# blimpy-2_0.net
KiCad netlist of a schematic drawn in EAGLE
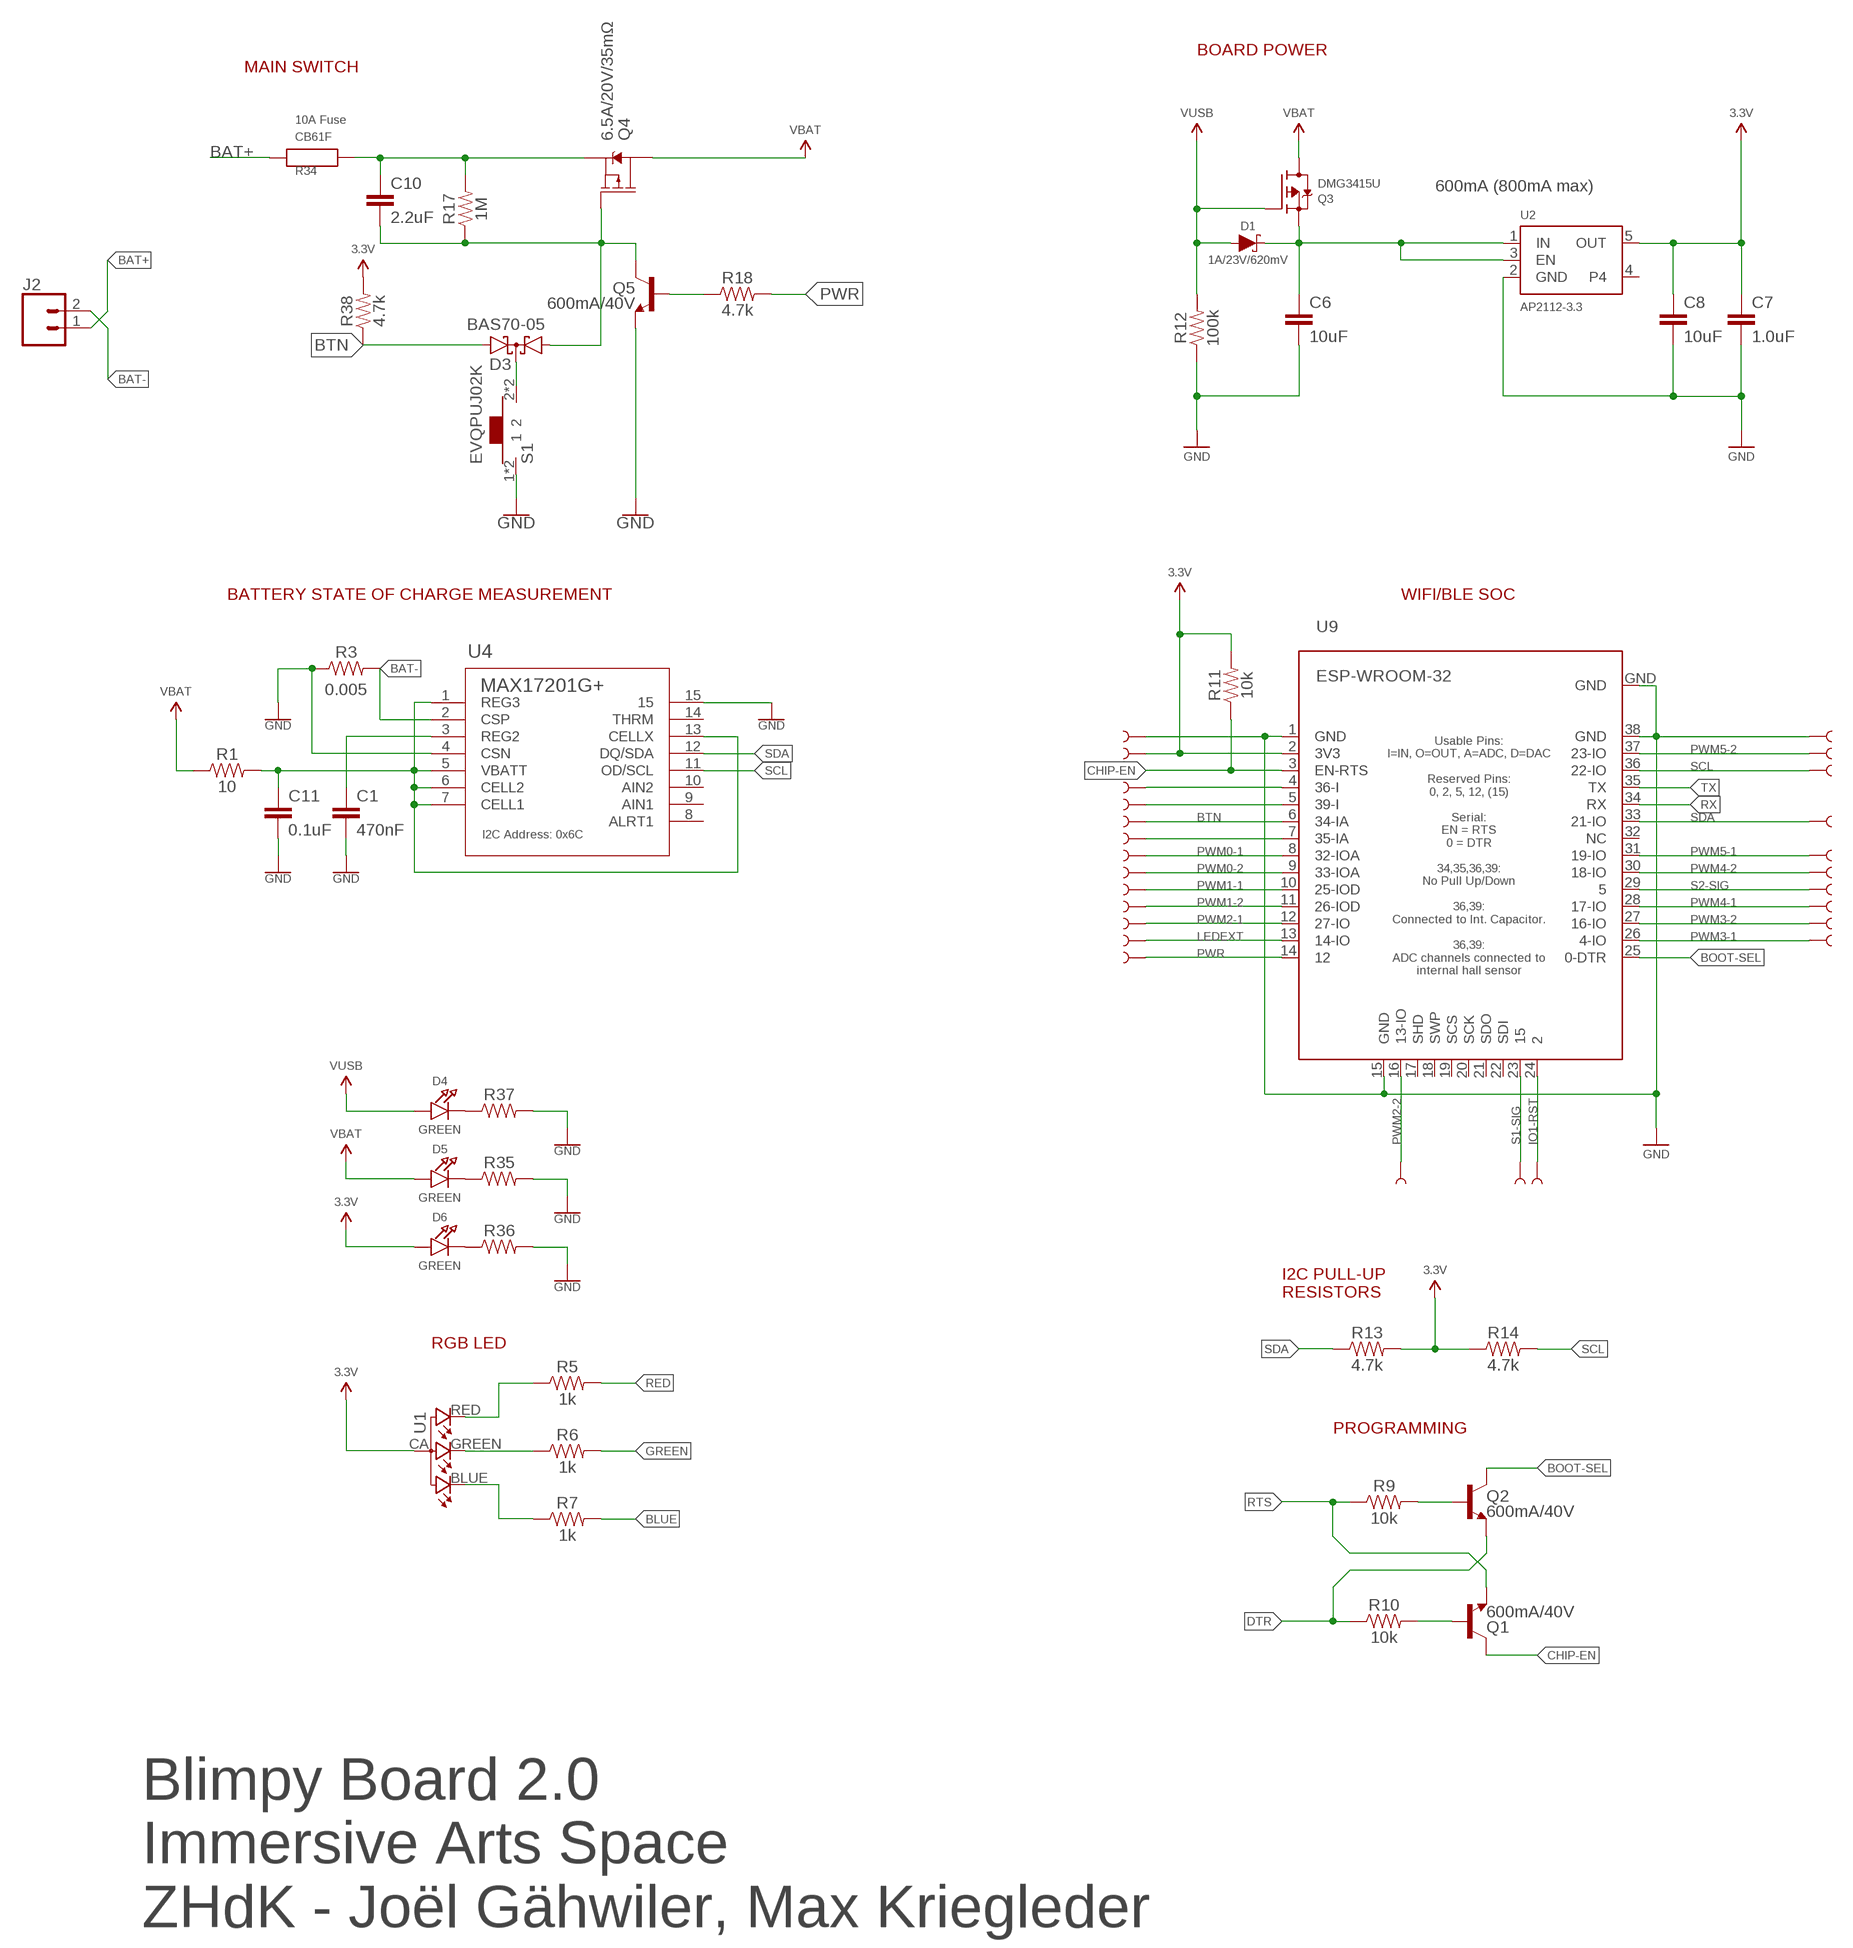
[diagram p0: schematic, sheet 1, part 1 of 2]
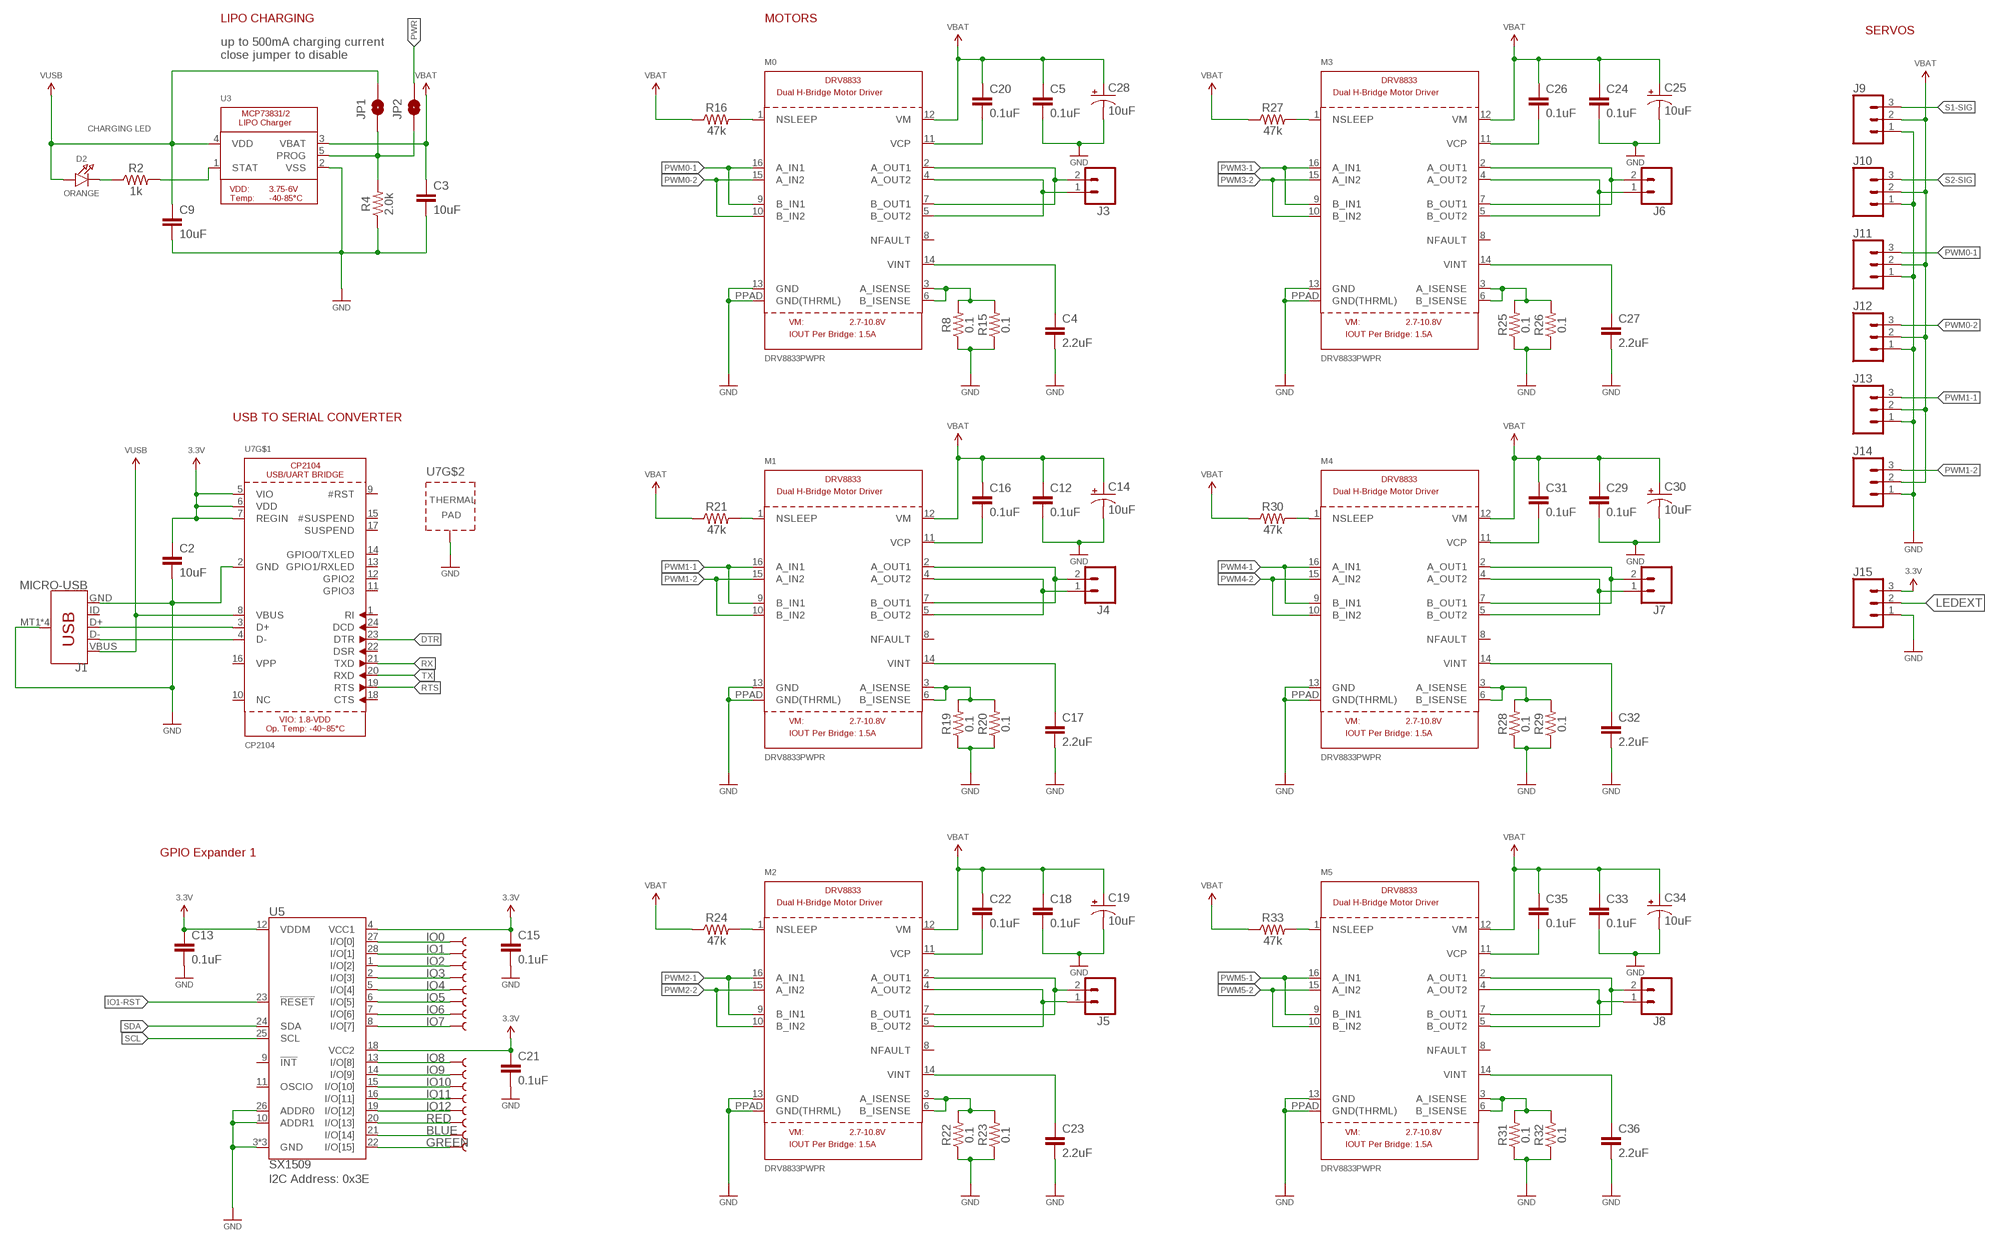
[diagram p1: schematic, sheet 1, part 2 of 2]

(export (version "E")
  (design (tool "Eeschema 10.0.6"))
  (components
    (comp (ref "C1")
      (value "470nF")
      (footprint "eagle-import:0603")
      (libsource (lib "eagle-import") (part "470NF-0608"))
    )
    (comp (ref "C2")
      (value "10uF")
      (footprint "eagle-import:0603")
      (libsource (lib "eagle-import") (part "10UF-0603-6.3V-20%"))
    )
    (comp (ref "C3")
      (value "10uF")
      (footprint "eagle-import:0603")
      (libsource (lib "eagle-import") (part "10UF-0603-6.3V-20%"))
    )
    (comp (ref "C4")
      (value "2.2uF")
      (footprint "eagle-import:0603")
      (libsource (lib "eagle-import") (part "2.2UF-0603-10V-20%"))
    )
    (comp (ref "C5")
      (value "0.1uF")
      (footprint "eagle-import:0603")
      (libsource (lib "eagle-import") (part "0.1UF-0603-25V-5%"))
    )
    (comp (ref "C6")
      (value "10uF")
      (footprint "eagle-import:0603")
      (libsource (lib "eagle-import") (part "10UF-0603-6.3V-20%"))
    )
    (comp (ref "C7")
      (value "1.0uF")
      (footprint "eagle-import:0603")
      (libsource (lib "eagle-import") (part "1.0UF-0603-16V-10%"))
    )
    (comp (ref "C8")
      (value "10uF")
      (footprint "eagle-import:0603")
      (libsource (lib "eagle-import") (part "10UF-0603-6.3V-20%"))
    )
    (comp (ref "C9")
      (value "10uF")
      (footprint "eagle-import:0603")
      (libsource (lib "eagle-import") (part "10UF-0603-6.3V-20%"))
    )
    (comp (ref "C10")
      (value "2.2uF")
      (footprint "eagle-import:0603")
      (libsource (lib "eagle-import") (part "2.2UF-0603-10V-20%"))
    )
    (comp (ref "C11")
      (value "0.1uF")
      (footprint "eagle-import:0603")
      (libsource (lib "eagle-import") (part "SparkFun-Capacitors_510_0.1UF-0603-25V-5%"))
    )
    (comp (ref "C12")
      (value "0.1uF")
      (footprint "eagle-import:0603")
      (libsource (lib "eagle-import") (part "0.1UF-0603-25V-5%"))
    )
    (comp (ref "C13")
      (value "0.1uF")
      (footprint "eagle-import:0603")
      (libsource (lib "eagle-import") (part "0.1UF-0603-25V-5%"))
    )
    (comp (ref "C14")
      (value "10uF")
      (footprint "eagle-import:EIA3216")
      (libsource (lib "eagle-import") (part "10UF-POLAR-EIA3216-16V-10%(TANT)"))
    )
    (comp (ref "C15")
      (value "0.1uF")
      (footprint "eagle-import:0603")
      (libsource (lib "eagle-import") (part "SparkFun-Capacitors_510_0.1UF-0603-25V-5%"))
    )
    (comp (ref "C16")
      (value "0.1uF")
      (footprint "eagle-import:0603")
      (libsource (lib "eagle-import") (part "0.1UF-0603-25V-5%"))
    )
    (comp (ref "C17")
      (value "2.2uF")
      (footprint "eagle-import:0603")
      (libsource (lib "eagle-import") (part "2.2UF-0603-10V-20%"))
    )
    (comp (ref "C18")
      (value "0.1uF")
      (footprint "eagle-import:0603")
      (libsource (lib "eagle-import") (part "0.1UF-0603-25V-5%"))
    )
    (comp (ref "C19")
      (value "10uF")
      (footprint "eagle-import:EIA3216")
      (libsource (lib "eagle-import") (part "10UF-POLAR-EIA3216-16V-10%(TANT)"))
    )
    (comp (ref "C20")
      (value "0.1uF")
      (footprint "eagle-import:0603")
      (libsource (lib "eagle-import") (part "0.1UF-0603-25V-5%"))
    )
    (comp (ref "C21")
      (value "0.1uF")
      (footprint "eagle-import:0603")
      (libsource (lib "eagle-import") (part "0.1UF-0603-25V-5%"))
    )
    (comp (ref "C22")
      (value "0.1uF")
      (footprint "eagle-import:0603")
      (libsource (lib "eagle-import") (part "0.1UF-0603-25V-5%"))
    )
    (comp (ref "C23")
      (value "2.2uF")
      (footprint "eagle-import:0603")
      (libsource (lib "eagle-import") (part "2.2UF-0603-10V-20%"))
    )
    (comp (ref "C24")
      (value "0.1uF")
      (footprint "eagle-import:0603")
      (libsource (lib "eagle-import") (part "0.1UF-0603-25V-5%"))
    )
    (comp (ref "C25")
      (value "10uF")
      (footprint "eagle-import:EIA3216")
      (libsource (lib "eagle-import") (part "10UF-POLAR-EIA3216-16V-10%(TANT)"))
    )
    (comp (ref "C26")
      (value "0.1uF")
      (footprint "eagle-import:0603")
      (libsource (lib "eagle-import") (part "0.1UF-0603-25V-5%"))
    )
    (comp (ref "C27")
      (value "2.2uF")
      (footprint "eagle-import:0603")
      (libsource (lib "eagle-import") (part "2.2UF-0603-10V-20%"))
    )
    (comp (ref "C28")
      (value "10uF")
      (footprint "eagle-import:EIA3216")
      (libsource (lib "eagle-import") (part "10UF-POLAR-EIA3216-16V-10%(TANT)"))
    )
    (comp (ref "C29")
      (value "0.1uF")
      (footprint "eagle-import:0603")
      (libsource (lib "eagle-import") (part "0.1UF-0603-25V-5%"))
    )
    (comp (ref "C30")
      (value "10uF")
      (footprint "eagle-import:EIA3216")
      (libsource (lib "eagle-import") (part "10UF-POLAR-EIA3216-16V-10%(TANT)"))
    )
    (comp (ref "C31")
      (value "0.1uF")
      (footprint "eagle-import:0603")
      (libsource (lib "eagle-import") (part "0.1UF-0603-25V-5%"))
    )
    (comp (ref "C32")
      (value "2.2uF")
      (footprint "eagle-import:0603")
      (libsource (lib "eagle-import") (part "2.2UF-0603-10V-20%"))
    )
    (comp (ref "C33")
      (value "0.1uF")
      (footprint "eagle-import:0603")
      (libsource (lib "eagle-import") (part "0.1UF-0603-25V-5%"))
    )
    (comp (ref "C34")
      (value "10uF")
      (footprint "eagle-import:EIA3216")
      (libsource (lib "eagle-import") (part "10UF-POLAR-EIA3216-16V-10%(TANT)"))
    )
    (comp (ref "C35")
      (value "0.1uF")
      (footprint "eagle-import:0603")
      (libsource (lib "eagle-import") (part "0.1UF-0603-25V-5%"))
    )
    (comp (ref "C36")
      (value "2.2uF")
      (footprint "eagle-import:0603")
      (libsource (lib "eagle-import") (part "2.2UF-0603-10V-20%"))
    )
    (comp (ref "D1")
      (value "1A/23V/620mV")
      (footprint "eagle-import:SOD-323")
      (libsource (lib "eagle-import") (part "DIODE-SCHOTTKY-BAT20J"))
    )
    (comp (ref "D2")
      (value "ORANGE")
      (footprint "eagle-import:CHIPLED_0805_NOOUTLINE")
      (libsource (lib "eagle-import") (part "LED0805_NOOUTLINE"))
    )
    (comp (ref "D3")
      (value "BAS70-05")
      (footprint "eagle-import:SOT23")
      (libsource (lib "eagle-import") (part "BAS70-05"))
    )
    (comp (ref "D4")
      (value "GREEN")
      (footprint "eagle-import:CHIPLED_0805_NOOUTLINE")
      (libsource (lib "eagle-import") (part "LED0805_NOOUTLINE"))
    )
    (comp (ref "D5")
      (value "GREEN")
      (footprint "eagle-import:CHIPLED_0805_NOOUTLINE")
      (libsource (lib "eagle-import") (part "LED0805_NOOUTLINE"))
    )
    (comp (ref "D6")
      (value "GREEN")
      (footprint "eagle-import:CHIPLED_0805_NOOUTLINE")
      (libsource (lib "eagle-import") (part "LED0805_NOOUTLINE"))
    )
    (comp (ref "J1")
      (value "MICRO-USB")
      (footprint "eagle-import:USB-MICROB")
      (libsource (lib "eagle-import") (part "USB_MICRO-B_SMT"))
    )
    (comp (ref "J2")
      (value "CONN_02PTH4")
      (footprint "eagle-import:1X02_XTRA_BIG")
      (libsource (lib "eagle-import") (part "CONN_02PTH4"))
    )
    (comp (ref "J3")
      (value "CONN_02-JST-2MM-SMT")
      (footprint "eagle-import:JST-2-SMD")
      (libsource (lib "eagle-import") (part "CONN_02-JST-2MM-SMT"))
    )
    (comp (ref "J4")
      (value "CONN_02-JST-2MM-SMT")
      (footprint "eagle-import:JST-2-SMD")
      (libsource (lib "eagle-import") (part "CONN_02-JST-2MM-SMT"))
    )
    (comp (ref "J5")
      (value "CONN_02-JST-2MM-SMT")
      (footprint "eagle-import:JST-2-SMD")
      (libsource (lib "eagle-import") (part "CONN_02-JST-2MM-SMT"))
    )
    (comp (ref "J6")
      (value "CONN_02-JST-2MM-SMT")
      (footprint "eagle-import:JST-2-SMD")
      (libsource (lib "eagle-import") (part "CONN_02-JST-2MM-SMT"))
    )
    (comp (ref "J7")
      (value "CONN_02-JST-2MM-SMT")
      (footprint "eagle-import:JST-2-SMD")
      (libsource (lib "eagle-import") (part "CONN_02-JST-2MM-SMT"))
    )
    (comp (ref "J8")
      (value "CONN_02-JST-2MM-SMT")
      (footprint "eagle-import:JST-2-SMD")
      (libsource (lib "eagle-import") (part "CONN_02-JST-2MM-SMT"))
    )
    (comp (ref "J9")
      (value "3-PIN SMD")
      (footprint "eagle-import:JST-3-SMD")
      (libsource (lib "eagle-import") (part "CONN_03JST-SMD"))
    )
    (comp (ref "J10")
      (value "3-PIN SMD")
      (footprint "eagle-import:JST-3-SMD")
      (libsource (lib "eagle-import") (part "CONN_03JST-SMD"))
    )
    (comp (ref "J11")
      (value "3-PIN SMD")
      (footprint "eagle-import:JST-3-SMD")
      (libsource (lib "eagle-import") (part "CONN_03JST-SMD"))
    )
    (comp (ref "J12")
      (value "3-PIN SMD")
      (footprint "eagle-import:JST-3-SMD")
      (libsource (lib "eagle-import") (part "CONN_03JST-SMD"))
    )
    (comp (ref "J13")
      (value "3-PIN SMD")
      (footprint "eagle-import:JST-3-SMD")
      (libsource (lib "eagle-import") (part "CONN_03JST-SMD"))
    )
    (comp (ref "J14")
      (value "3-PIN SMD")
      (footprint "eagle-import:JST-3-SMD")
      (libsource (lib "eagle-import") (part "CONN_03JST-SMD"))
    )
    (comp (ref "J15")
      (value "3-PIN SMD")
      (footprint "eagle-import:JST-3-SMD")
      (libsource (lib "eagle-import") (part "CONN_03JST-SMD"))
    )
    (comp (ref "JP1")
      (value "JUMPER-SMT_2_NO_SILK")
      (footprint "eagle-import:SMT-JUMPER_2_NO_SILK")
      (libsource (lib "eagle-import") (part "JUMPER-SMT_2_NO_SILK"))
    )
    (comp (ref "JP2")
      (value "JUMPER-SMT_2_NO_SILK")
      (footprint "eagle-import:SMT-JUMPER_2_NO_SILK")
      (libsource (lib "eagle-import") (part "JUMPER-SMT_2_NO_SILK"))
    )
    (comp (ref "M0")
      (value "DRV8833PWPR")
      (footprint "eagle-import:HTSSOP16")
      (libsource (lib "eagle-import") (part "DRV8833"))
    )
    (comp (ref "M1")
      (value "DRV8833PWPR")
      (footprint "eagle-import:HTSSOP16")
      (libsource (lib "eagle-import") (part "DRV8833"))
    )
    (comp (ref "M2")
      (value "DRV8833PWPR")
      (footprint "eagle-import:HTSSOP16")
      (libsource (lib "eagle-import") (part "DRV8833"))
    )
    (comp (ref "M3")
      (value "DRV8833PWPR")
      (footprint "eagle-import:HTSSOP16")
      (libsource (lib "eagle-import") (part "DRV8833"))
    )
    (comp (ref "M4")
      (value "DRV8833PWPR")
      (footprint "eagle-import:HTSSOP16")
      (libsource (lib "eagle-import") (part "DRV8833"))
    )
    (comp (ref "M5")
      (value "DRV8833PWPR")
      (footprint "eagle-import:HTSSOP16")
      (libsource (lib "eagle-import") (part "DRV8833"))
    )
    (comp (ref "Q1")
      (value "600mA/40V")
      (footprint "eagle-import:SOT23-3")
      (libsource (lib "eagle-import") (part "TRANS_NPN-MMBT2222AL"))
    )
    (comp (ref "Q2")
      (value "600mA/40V")
      (footprint "eagle-import:SOT23-3")
      (libsource (lib "eagle-import") (part "TRANS_NPN-MMBT2222AL"))
    )
    (comp (ref "Q3")
      (value "DMG3415U")
      (footprint "eagle-import:SOT23-R")
      (libsource (lib "eagle-import") (part "MOSFET-P"))
    )
    (comp (ref "Q4")
      (value "6.5A/20V/35mΩ")
      (footprint "eagle-import:SO08")
      (libsource (lib "eagle-import") (part "MOSFET_PCH-NDS8434"))
    )
    (comp (ref "Q5")
      (value "600mA/40V")
      (footprint "eagle-import:SOT23-3")
      (libsource (lib "eagle-import") (part "TRANS_NPN-MMBT2222AL"))
    )
    (comp (ref "R1")
      (value "10")
      (footprint "eagle-import:0603")
      (libsource (lib "eagle-import") (part "10OHM-0603-1/10W-1%"))
    )
    (comp (ref "R2")
      (value "1k")
      (footprint "eagle-import:0603")
      (libsource (lib "eagle-import") (part "1KOHM-0603-1/10W-1%"))
    )
    (comp (ref "R3")
      (value "0.005")
      (footprint "eagle-import:1206")
      (libsource (lib "eagle-import") (part "RESISTOR1206"))
    )
    (comp (ref "R4")
      (value "2.0k")
      (footprint "eagle-import:0603")
      (libsource (lib "eagle-import") (part "2.0KOHM-0603-1/10W-5%"))
    )
    (comp (ref "R5")
      (value "1k")
      (footprint "eagle-import:0603")
      (libsource (lib "eagle-import") (part "1KOHM-0603-1/10W-1%"))
    )
    (comp (ref "R6")
      (value "1k")
      (footprint "eagle-import:0603")
      (libsource (lib "eagle-import") (part "1KOHM-0603-1/10W-1%"))
    )
    (comp (ref "R7")
      (value "1k")
      (footprint "eagle-import:0603")
      (libsource (lib "eagle-import") (part "1KOHM-0603-1/10W-1%"))
    )
    (comp (ref "R8")
      (value "0.1")
      (footprint "eagle-import:1206")
      (libsource (lib "eagle-import") (part "RESISTOR1206"))
    )
    (comp (ref "R9")
      (value "10k")
      (footprint "eagle-import:0603")
      (libsource (lib "eagle-import") (part "10KOHM-0603-1/10W-1%"))
    )
    (comp (ref "R10")
      (value "10k")
      (footprint "eagle-import:0603")
      (libsource (lib "eagle-import") (part "10KOHM-0603-1/10W-1%"))
    )
    (comp (ref "R11")
      (value "10k")
      (footprint "eagle-import:0603")
      (libsource (lib "eagle-import") (part "10KOHM-0603-1/10W-1%"))
    )
    (comp (ref "R12")
      (value "100k")
      (footprint "eagle-import:0603")
      (libsource (lib "eagle-import") (part "100KOHM-0603-1/10W-1%"))
    )
    (comp (ref "R13")
      (value "4.7k")
      (footprint "eagle-import:0603")
      (libsource (lib "eagle-import") (part "4.7KOHM-0603-1/10W-1%"))
    )
    (comp (ref "R14")
      (value "4.7k")
      (footprint "eagle-import:0603")
      (libsource (lib "eagle-import") (part "4.7KOHM-0603-1/10W-1%"))
    )
    (comp (ref "R15")
      (value "0.1")
      (footprint "eagle-import:1206")
      (libsource (lib "eagle-import") (part "RESISTOR1206"))
    )
    (comp (ref "R16")
      (value "47k")
      (footprint "eagle-import:0603")
      (libsource (lib "eagle-import") (part "47KOHM-0603-1/10W-1%"))
    )
    (comp (ref "R17")
      (value "1M")
      (footprint "eagle-import:0603")
      (libsource (lib "eagle-import") (part "1MOHM-0603-1/4W-5%"))
    )
    (comp (ref "R18")
      (value "4.7k")
      (footprint "eagle-import:0603")
      (libsource (lib "eagle-import") (part "SparkFun-Resistors_532_4.7KOHM-0603-1/10W-1%"))
    )
    (comp (ref "R19")
      (value "0.1")
      (footprint "eagle-import:1206")
      (libsource (lib "eagle-import") (part "RESISTOR1206"))
    )
    (comp (ref "R20")
      (value "0.1")
      (footprint "eagle-import:1206")
      (libsource (lib "eagle-import") (part "RESISTOR1206"))
    )
    (comp (ref "R21")
      (value "47k")
      (footprint "eagle-import:0603")
      (libsource (lib "eagle-import") (part "47KOHM-0603-1/10W-1%"))
    )
    (comp (ref "R22")
      (value "0.1")
      (footprint "eagle-import:1206")
      (libsource (lib "eagle-import") (part "RESISTOR1206"))
    )
    (comp (ref "R23")
      (value "0.1")
      (footprint "eagle-import:1206")
      (libsource (lib "eagle-import") (part "RESISTOR1206"))
    )
    (comp (ref "R24")
      (value "47k")
      (footprint "eagle-import:0603")
      (libsource (lib "eagle-import") (part "47KOHM-0603-1/10W-1%"))
    )
    (comp (ref "R25")
      (value "0.1")
      (footprint "eagle-import:1206")
      (libsource (lib "eagle-import") (part "RESISTOR1206"))
    )
    (comp (ref "R26")
      (value "0.1")
      (footprint "eagle-import:1206")
      (libsource (lib "eagle-import") (part "RESISTOR1206"))
    )
    (comp (ref "R27")
      (value "47k")
      (footprint "eagle-import:0603")
      (libsource (lib "eagle-import") (part "47KOHM-0603-1/10W-1%"))
    )
    (comp (ref "R28")
      (value "0.1")
      (footprint "eagle-import:1206")
      (libsource (lib "eagle-import") (part "RESISTOR1206"))
    )
    (comp (ref "R29")
      (value "0.1")
      (footprint "eagle-import:1206")
      (libsource (lib "eagle-import") (part "RESISTOR1206"))
    )
    (comp (ref "R30")
      (value "47k")
      (footprint "eagle-import:0603")
      (libsource (lib "eagle-import") (part "47KOHM-0603-1/10W-1%"))
    )
    (comp (ref "R31")
      (value "0.1")
      (footprint "eagle-import:1206")
      (libsource (lib "eagle-import") (part "RESISTOR1206"))
    )
    (comp (ref "R32")
      (value "0.1")
      (footprint "eagle-import:1206")
      (libsource (lib "eagle-import") (part "RESISTOR1206"))
    )
    (comp (ref "R33")
      (value "47k")
      (footprint "eagle-import:0603")
      (libsource (lib "eagle-import") (part "47KOHM-0603-1/10W-1%"))
    )
    (comp (ref "R34")
      (value "CB61F")
      (footprint "eagle-import:CB61F")
      (libsource (lib "eagle-import") (part "CB61F"))
    )
    (comp (ref "R35")
      (value "RESISTOR0603")
      (footprint "eagle-import:0603")
      (libsource (lib "eagle-import") (part "RESISTOR0603"))
    )
    (comp (ref "R36")
      (value "RESISTOR0603")
      (footprint "eagle-import:0603")
      (libsource (lib "eagle-import") (part "RESISTOR0603"))
    )
    (comp (ref "R37")
      (value "RESISTOR0603")
      (footprint "eagle-import:0603")
      (libsource (lib "eagle-import") (part "RESISTOR0603"))
    )
    (comp (ref "R38")
      (value "4.7k")
      (footprint "eagle-import:0603")
      (libsource (lib "eagle-import") (part "1MOHM-0603-1/4W-5%"))
    )
    (comp (ref "S1")
      (value "EVQPUJ02K")
      (footprint "eagle-import:EVQPUJ02K")
      (libsource (lib "eagle-import") (part "EVQPUJ02K"))
    )
    (comp (ref "TP1")
      (value "TEST-POINT3")
      (footprint "eagle-import:PAD.03X.03")
      (libsource (lib "eagle-import") (part "TEST-POINT3"))
    )
    (comp (ref "TP2")
      (value "TEST-POINT3")
      (footprint "eagle-import:PAD.03X.03")
      (libsource (lib "eagle-import") (part "TEST-POINT3"))
    )
    (comp (ref "TP3")
      (value "TEST-POINT3")
      (footprint "eagle-import:PAD.03X.03")
      (libsource (lib "eagle-import") (part "TEST-POINT3"))
    )
    (comp (ref "TP4")
      (value "TEST-POINT3")
      (footprint "eagle-import:PAD.03X.03")
      (libsource (lib "eagle-import") (part "TEST-POINT3"))
    )
    (comp (ref "TP5")
      (value "TEST-POINT3")
      (footprint "eagle-import:PAD.03X.03")
      (libsource (lib "eagle-import") (part "TEST-POINT3"))
    )
    (comp (ref "TP6")
      (value "TEST-POINT3")
      (footprint "eagle-import:PAD.03X.03")
      (libsource (lib "eagle-import") (part "TEST-POINT3"))
    )
    (comp (ref "TP7")
      (value "TEST-POINT3")
      (footprint "eagle-import:PAD.03X.03")
      (libsource (lib "eagle-import") (part "TEST-POINT3"))
    )
    (comp (ref "TP8")
      (value "TEST-POINT3")
      (footprint "eagle-import:PAD.03X.03")
      (libsource (lib "eagle-import") (part "TEST-POINT3"))
    )
    (comp (ref "TP9")
      (value "TEST-POINT3")
      (footprint "eagle-import:PAD.03X.03")
      (libsource (lib "eagle-import") (part "TEST-POINT3"))
    )
    (comp (ref "TP10")
      (value "TEST-POINT3")
      (footprint "eagle-import:PAD.03X.03")
      (libsource (lib "eagle-import") (part "TEST-POINT3"))
    )
    (comp (ref "TP11")
      (value "TEST-POINT3")
      (footprint "eagle-import:PAD.03X.03")
      (libsource (lib "eagle-import") (part "TEST-POINT3"))
    )
    (comp (ref "TP12")
      (value "TEST-POINT3")
      (footprint "eagle-import:PAD.03X.03")
      (libsource (lib "eagle-import") (part "TEST-POINT3"))
    )
    (comp (ref "TP13")
      (value "TEST-POINT3")
      (footprint "eagle-import:PAD.03X.03")
      (libsource (lib "eagle-import") (part "TEST-POINT3"))
    )
    (comp (ref "TP14")
      (value "TEST-POINT3")
      (footprint "eagle-import:PAD.03X.03")
      (libsource (lib "eagle-import") (part "TEST-POINT3"))
    )
    (comp (ref "TP15")
      (value "TEST-POINT3")
      (footprint "eagle-import:PAD.03X.03")
      (libsource (lib "eagle-import") (part "TEST-POINT3"))
    )
    (comp (ref "TP16")
      (value "TEST-POINT3")
      (footprint "eagle-import:PAD.03X.03")
      (libsource (lib "eagle-import") (part "TEST-POINT3"))
    )
    (comp (ref "TP17")
      (value "TEST-POINT3")
      (footprint "eagle-import:PAD.03X.03")
      (libsource (lib "eagle-import") (part "TEST-POINT3"))
    )
    (comp (ref "TP18")
      (value "TEST-POINT3")
      (footprint "eagle-import:PAD.03X.03")
      (libsource (lib "eagle-import") (part "TEST-POINT3"))
    )
    (comp (ref "TP19")
      (value "TEST-POINT3")
      (footprint "eagle-import:PAD.03X.03")
      (libsource (lib "eagle-import") (part "TEST-POINT3"))
    )
    (comp (ref "TP20")
      (value "TEST-POINT3")
      (footprint "eagle-import:PAD.03X.03")
      (libsource (lib "eagle-import") (part "TEST-POINT3"))
    )
    (comp (ref "TP21")
      (value "TEST-POINT3")
      (footprint "eagle-import:PAD.03X.03")
      (libsource (lib "eagle-import") (part "TEST-POINT3"))
    )
    (comp (ref "TP22")
      (value "TEST-POINT3")
      (footprint "eagle-import:PAD.03X.03")
      (libsource (lib "eagle-import") (part "TEST-POINT3"))
    )
    (comp (ref "TP23")
      (value "TEST-POINT3")
      (footprint "eagle-import:PAD.03X.03")
      (libsource (lib "eagle-import") (part "TEST-POINT3"))
    )
    (comp (ref "TP24")
      (value "TEST-POINT3")
      (footprint "eagle-import:PAD.03X.03")
      (libsource (lib "eagle-import") (part "TEST-POINT3"))
    )
    (comp (ref "TP25")
      (value "TEST-POINT3")
      (footprint "eagle-import:PAD.03X.03")
      (libsource (lib "eagle-import") (part "TEST-POINT3"))
    )
    (comp (ref "TP26")
      (value "TEST-POINT3")
      (footprint "eagle-import:PAD.03X.03")
      (libsource (lib "eagle-import") (part "TEST-POINT3"))
    )
    (comp (ref "TP27")
      (value "TEST-POINT3")
      (footprint "eagle-import:PAD.03X.03")
      (libsource (lib "eagle-import") (part "TEST-POINT3"))
    )
    (comp (ref "TP28")
      (value "TEST-POINT3")
      (footprint "eagle-import:PAD.03X.03")
      (libsource (lib "eagle-import") (part "TEST-POINT3"))
    )
    (comp (ref "TP29")
      (value "TEST-POINT3")
      (footprint "eagle-import:PAD.03X.03")
      (libsource (lib "eagle-import") (part "TEST-POINT3"))
    )
    (comp (ref "TP30")
      (value "TEST-POINT3")
      (footprint "eagle-import:PAD.03X.03")
      (libsource (lib "eagle-import") (part "TEST-POINT3"))
    )
    (comp (ref "TP31")
      (value "TEST-POINT3")
      (footprint "eagle-import:PAD.03X.03")
      (libsource (lib "eagle-import") (part "TEST-POINT3"))
    )
    (comp (ref "TP32")
      (value "TEST-POINT3")
      (footprint "eagle-import:PAD.03X.03")
      (libsource (lib "eagle-import") (part "TEST-POINT3"))
    )
    (comp (ref "TP33")
      (value "TEST-POINT3")
      (footprint "eagle-import:PAD.03X.03")
      (libsource (lib "eagle-import") (part "TEST-POINT3"))
    )
    (comp (ref "TP34")
      (value "TEST-POINT3")
      (footprint "eagle-import:PAD.03X.03")
      (libsource (lib "eagle-import") (part "TEST-POINT3"))
    )
    (comp (ref "TP35")
      (value "TEST-POINT3")
      (footprint "eagle-import:PAD.03X.03")
      (libsource (lib "eagle-import") (part "TEST-POINT3"))
    )
    (comp (ref "TP36")
      (value "TEST-POINT3")
      (footprint "eagle-import:PAD.03X.03")
      (libsource (lib "eagle-import") (part "TEST-POINT3"))
    )
    (comp (ref "TP37")
      (value "TEST-POINT3")
      (footprint "eagle-import:PAD.03X.03")
      (libsource (lib "eagle-import") (part "TEST-POINT3"))
    )
    (comp (ref "TP38")
      (value "TEST-POINT3")
      (footprint "eagle-import:PAD.03X.03")
      (libsource (lib "eagle-import") (part "TEST-POINT3"))
    )
    (comp (ref "TP39")
      (value "TEST-POINT3")
      (footprint "eagle-import:PAD.03X.03")
      (libsource (lib "eagle-import") (part "TEST-POINT3"))
    )
    (comp (ref "TP40")
      (value "TEST-POINT3")
      (footprint "eagle-import:PAD.03X.03")
      (libsource (lib "eagle-import") (part "TEST-POINT3"))
    )
    (comp (ref "TP41")
      (value "TEST-POINT3")
      (footprint "eagle-import:PAD.03X.03")
      (libsource (lib "eagle-import") (part "TEST-POINT3"))
    )
    (comp (ref "TP42")
      (value "TEST-POINT3")
      (footprint "eagle-import:PAD.03X.03")
      (libsource (lib "eagle-import") (part "TEST-POINT3"))
    )
    (comp (ref "U1")
      (value "PARTICLE_RGB-LED-CLMVB-FKARGB")
      (footprint "eagle-import:PARTICLE_PLCC4-2MM-RGB")
      (libsource (lib "eagle-import") (part "PARTICLE_RGB-LED-CLMVB-FKARGB"))
    )
    (comp (ref "U2")
      (value "AP2112-3.3")
      (footprint "eagle-import:SOT23-5")
      (libsource (lib "eagle-import") (part "VREG_SOT23-5"))
    )
    (comp (ref "U3")
      (value "MICROBUILDER_MCP73831/2")
      (footprint "eagle-import:MICROBUILDER_SOT23-5")
      (libsource (lib "eagle-import") (part "MICROBUILDER_MCP73831/2"))
    )
    (comp (ref "U4")
      (value "MAX17201G+")
      (footprint "eagle-import:21-0137I_T1433-1_MXM")
      (fields (field (name "COPYRIGHT") "Copyright (C) 2018 Accelerated Designs. All rights reserved"))
      (libsource (lib "eagle-import") (part "MAX17201G+"))
    )
    (comp (ref "U5")
      (value "SX1509")
      (footprint "eagle-import:QFN-28")
      (libsource (lib "eagle-import") (part "SX1509"))
    )
    (comp (ref "U7")
      (value "CP2104")
      (footprint "eagle-import:QFN24_4MM_SMSC")
      (libsource (lib "eagle-import") (part "CP2104"))
    )
    (comp (ref "U9")
      (value "ESP-WROOM-32")
      (footprint "eagle-import:ESP-WROOM-32")
      (libsource (lib "eagle-import") (part "ESP-WROOM-32"))
    )
  )
  (nets
    (net (code "1") (name "/IO0") (class "Default")
      (node (ref "TP27") (pin "P$1") (pinfunction "1_P$1") (pintype "bidirectional"))
      (node (ref "U5") (pin "27") (pinfunction "I/O[0]_27") (pintype "bidirectional"))
    )
    (net (code "2") (name "/IO1") (class "Default")
      (node (ref "TP28") (pin "P$1") (pinfunction "1_P$1") (pintype "bidirectional"))
      (node (ref "U5") (pin "28") (pinfunction "I/O[1]_28") (pintype "bidirectional"))
    )
    (net (code "3") (name "/IO2") (class "Default")
      (node (ref "TP29") (pin "P$1") (pinfunction "1_P$1") (pintype "bidirectional"))
      (node (ref "U5") (pin "1") (pinfunction "I/O[2]_1") (pintype "bidirectional"))
    )
    (net (code "4") (name "/IO3") (class "Default")
      (node (ref "TP30") (pin "P$1") (pinfunction "1_P$1") (pintype "bidirectional"))
      (node (ref "U5") (pin "2") (pinfunction "I/O[3]_2") (pintype "bidirectional"))
    )
    (net (code "5") (name "/IO4") (class "Default")
      (node (ref "TP31") (pin "P$1") (pinfunction "1_P$1") (pintype "bidirectional"))
      (node (ref "U5") (pin "5") (pinfunction "I/O[4]_5") (pintype "bidirectional"))
    )
    (net (code "6") (name "/IO5") (class "Default")
      (node (ref "TP32") (pin "P$1") (pinfunction "1_P$1") (pintype "bidirectional"))
      (node (ref "U5") (pin "6") (pinfunction "I/O[5]_6") (pintype "bidirectional"))
    )
    (net (code "7") (name "/IO6") (class "Default")
      (node (ref "TP33") (pin "P$1") (pinfunction "1_P$1") (pintype "bidirectional"))
      (node (ref "U5") (pin "7") (pinfunction "I/O[6]_7") (pintype "bidirectional"))
    )
    (net (code "8") (name "/IO7") (class "Default")
      (node (ref "TP34") (pin "P$1") (pinfunction "1_P$1") (pintype "bidirectional"))
      (node (ref "U5") (pin "8") (pinfunction "I/O[7]_8") (pintype "bidirectional"))
    )
    (net (code "9") (name "/IO8") (class "Default")
      (node (ref "TP35") (pin "P$1") (pinfunction "1_P$1") (pintype "bidirectional"))
      (node (ref "U5") (pin "13") (pinfunction "I/O[8]_13") (pintype "bidirectional"))
    )
    (net (code "10") (name "/IO9") (class "Default")
      (node (ref "TP36") (pin "P$1") (pinfunction "1_P$1") (pintype "bidirectional"))
      (node (ref "U5") (pin "14") (pinfunction "I/O[9]_14") (pintype "bidirectional"))
    )
    (net (code "11") (name "/IO10") (class "Default")
      (node (ref "TP37") (pin "P$1") (pinfunction "1_P$1") (pintype "bidirectional"))
      (node (ref "U5") (pin "15") (pinfunction "I/O[10]_15") (pintype "bidirectional"))
    )
    (net (code "12") (name "/IO11") (class "Default")
      (node (ref "TP38") (pin "P$1") (pinfunction "1_P$1") (pintype "bidirectional"))
      (node (ref "U5") (pin "16") (pinfunction "I/O[11]_16") (pintype "bidirectional"))
    )
    (net (code "13") (name "/IO12") (class "Default")
      (node (ref "TP39") (pin "P$1") (pinfunction "1_P$1") (pintype "bidirectional"))
      (node (ref "U5") (pin "19") (pinfunction "I/O[12]_19") (pintype "bidirectional"))
    )
    (net (code "14") (name "3.3V") (class "Default")
      (node (ref "C13") (pin "1") (pinfunction "1_1") (pintype "passive"))
      (node (ref "C15") (pin "1") (pinfunction "1_1") (pintype "passive"))
      (node (ref "C2") (pin "1") (pinfunction "1_1") (pintype "passive"))
      (node (ref "C21") (pin "1") (pinfunction "1_1") (pintype "passive"))
      (node (ref "C7") (pin "1") (pinfunction "1_1") (pintype "passive"))
      (node (ref "C8") (pin "1") (pinfunction "1_1") (pintype "passive"))
      (node (ref "D6") (pin "A") (pinfunction "A_A") (pintype "passive"))
      (node (ref "J15") (pin "3") (pinfunction "3_3") (pintype "passive"))
      (node (ref "R11") (pin "2") (pinfunction "2_2") (pintype "passive"))
      (node (ref "R13") (pin "2") (pinfunction "2_2") (pintype "passive"))
      (node (ref "R14") (pin "1") (pinfunction "1_1") (pintype "passive"))
      (node (ref "R38") (pin "2") (pinfunction "2_2") (pintype "passive"))
      (node (ref "TP11") (pin "P$1") (pinfunction "1_P$1") (pintype "bidirectional"))
      (node (ref "U1") (pin "CA") (pinfunction "1_CA") (pintype "passive"))
      (node (ref "U2") (pin "5") (pinfunction "OUT_5") (pintype "power_in"))
      (node (ref "U5") (pin "12") (pinfunction "VDDM_12") (pintype "bidirectional"))
      (node (ref "U5") (pin "18") (pinfunction "VCC2_18") (pintype "bidirectional"))
      (node (ref "U5") (pin "4") (pinfunction "VCC1_4") (pintype "bidirectional"))
      (node (ref "U7") (pin "5") (pinfunction "VIO_5") (pintype "power_in"))
      (node (ref "U7") (pin "6") (pinfunction "VDD_6") (pintype "power_in"))
      (node (ref "U7") (pin "7") (pinfunction "REGIN_7") (pintype "power_in"))
      (node (ref "U9") (pin "2") (pinfunction "3V3_2") (pintype "bidirectional"))
    )
    (net (code "15") (name "BAT+") (class "Default")
      (node (ref "J2") (pin "1") (pinfunction "1_1") (pintype "passive"))
      (node (ref "R34") (pin "1") (pinfunction "1_1") (pintype "passive"))
    )
    (net (code "16") (name "BAT-") (class "Default")
      (node (ref "J2") (pin "2") (pinfunction "2_2") (pintype "passive"))
      (node (ref "R3") (pin "2") (pinfunction "2_2") (pintype "passive"))
      (node (ref "U4") (pin "2") (pinfunction "CSP_2") (pintype "passive"))
    )
    (net (code "17") (name "BLUE") (class "Default")
      (node (ref "R7") (pin "2") (pinfunction "2_2") (pintype "passive"))
      (node (ref "TP41") (pin "P$1") (pinfunction "1_P$1") (pintype "bidirectional"))
      (node (ref "U5") (pin "21") (pinfunction "I/O[14]_21") (pintype "bidirectional"))
    )
    (net (code "18") (name "BOOT-SEL") (class "Default")
      (node (ref "Q2") (pin "3") (pinfunction "C_3") (pintype "passive"))
      (node (ref "U9") (pin "25") (pinfunction "0-DTR_25") (pintype "bidirectional"))
    )
    (net (code "19") (name "BTN") (class "Default")
      (node (ref "D3") (pin "2") (pinfunction "A2_2") (pintype "passive"))
      (node (ref "R38") (pin "1") (pinfunction "1_1") (pintype "passive"))
      (node (ref "TP8") (pin "P$1") (pinfunction "1_P$1") (pintype "bidirectional"))
      (node (ref "U9") (pin "6") (pinfunction "34-IA_6") (pintype "bidirectional"))
    )
    (net (code "20") (name "CHIP-EN") (class "Default")
      (node (ref "Q1") (pin "3") (pinfunction "C_3") (pintype "passive"))
      (node (ref "R11") (pin "1") (pinfunction "1_1") (pintype "passive"))
      (node (ref "U9") (pin "3") (pinfunction "EN-RTS_3") (pintype "bidirectional"))
    )
    (net (code "21") (name "DTR") (class "Default")
      (node (ref "Q2") (pin "2") (pinfunction "E_2") (pintype "passive"))
      (node (ref "R10") (pin "1") (pinfunction "1_1") (pintype "passive"))
      (node (ref "U7") (pin "23") (pinfunction "DTR_23") (pintype "output"))
    )
    (net (code "22") (name "GND") (class "Default")
      (node (ref "C1") (pin "2") (pinfunction "2_2") (pintype "passive"))
      (node (ref "C11") (pin "2") (pinfunction "2_2") (pintype "passive"))
      (node (ref "C12") (pin "2") (pinfunction "2_2") (pintype "passive"))
      (node (ref "C13") (pin "2") (pinfunction "2_2") (pintype "passive"))
      (node (ref "C14") (pin "-") (pinfunction "-_-") (pintype "passive"))
      (node (ref "C15") (pin "2") (pinfunction "2_2") (pintype "passive"))
      (node (ref "C17") (pin "2") (pinfunction "2_2") (pintype "passive"))
      (node (ref "C18") (pin "2") (pinfunction "2_2") (pintype "passive"))
      (node (ref "C19") (pin "-") (pinfunction "-_-") (pintype "passive"))
      (node (ref "C2") (pin "2") (pinfunction "2_2") (pintype "passive"))
      (node (ref "C21") (pin "2") (pinfunction "2_2") (pintype "passive"))
      (node (ref "C23") (pin "2") (pinfunction "2_2") (pintype "passive"))
      (node (ref "C24") (pin "2") (pinfunction "2_2") (pintype "passive"))
      (node (ref "C25") (pin "-") (pinfunction "-_-") (pintype "passive"))
      (node (ref "C27") (pin "2") (pinfunction "2_2") (pintype "passive"))
      (node (ref "C28") (pin "-") (pinfunction "-_-") (pintype "passive"))
      (node (ref "C29") (pin "2") (pinfunction "2_2") (pintype "passive"))
      (node (ref "C3") (pin "2") (pinfunction "2_2") (pintype "passive"))
      (node (ref "C30") (pin "-") (pinfunction "-_-") (pintype "passive"))
      (node (ref "C32") (pin "2") (pinfunction "2_2") (pintype "passive"))
      (node (ref "C33") (pin "2") (pinfunction "2_2") (pintype "passive"))
      (node (ref "C34") (pin "-") (pinfunction "-_-") (pintype "passive"))
      (node (ref "C36") (pin "2") (pinfunction "2_2") (pintype "passive"))
      (node (ref "C4") (pin "2") (pinfunction "2_2") (pintype "passive"))
      (node (ref "C5") (pin "2") (pinfunction "2_2") (pintype "passive"))
      (node (ref "C6") (pin "2") (pinfunction "2_2") (pintype "passive"))
      (node (ref "C7") (pin "2") (pinfunction "2_2") (pintype "passive"))
      (node (ref "C8") (pin "2") (pinfunction "2_2") (pintype "passive"))
      (node (ref "C9") (pin "2") (pinfunction "2_2") (pintype "passive"))
      (node (ref "J1") (pin "GND") (pinfunction "GND_GND") (pintype "power_in"))
      (node (ref "J1") (pin "MT1") (pinfunction "SHIELD_MT1") (pintype "bidirectional"))
      (node (ref "J1") (pin "MT2") (pinfunction "SHIELD_MT2") (pintype "bidirectional"))
      (node (ref "J1") (pin "P$1") (pinfunction "SHIELD_P$1") (pintype "bidirectional"))
      (node (ref "J1") (pin "P$2") (pinfunction "SHIELD_P$2") (pintype "bidirectional"))
      (node (ref "J10") (pin "1") (pinfunction "1_1") (pintype "passive"))
      (node (ref "J11") (pin "1") (pinfunction "1_1") (pintype "passive"))
      (node (ref "J12") (pin "1") (pinfunction "1_1") (pintype "passive"))
      (node (ref "J13") (pin "1") (pinfunction "1_1") (pintype "passive"))
      (node (ref "J14") (pin "1") (pinfunction "1_1") (pintype "passive"))
      (node (ref "J15") (pin "1") (pinfunction "1_1") (pintype "passive"))
      (node (ref "J9") (pin "1") (pinfunction "1_1") (pintype "passive"))
      (node (ref "M0") (pin "13") (pinfunction "GND_13") (pintype "power_in"))
      (node (ref "M0") (pin "PPAD") (pinfunction "GND(THRML)_PPAD") (pintype "power_in"))
      (node (ref "M1") (pin "13") (pinfunction "GND_13") (pintype "power_in"))
      (node (ref "M1") (pin "PPAD") (pinfunction "GND(THRML)_PPAD") (pintype "power_in"))
      (node (ref "M2") (pin "13") (pinfunction "GND_13") (pintype "power_in"))
      (node (ref "M2") (pin "PPAD") (pinfunction "GND(THRML)_PPAD") (pintype "power_in"))
      (node (ref "M3") (pin "13") (pinfunction "GND_13") (pintype "power_in"))
      (node (ref "M3") (pin "PPAD") (pinfunction "GND(THRML)_PPAD") (pintype "power_in"))
      (node (ref "M4") (pin "13") (pinfunction "GND_13") (pintype "power_in"))
      (node (ref "M4") (pin "PPAD") (pinfunction "GND(THRML)_PPAD") (pintype "power_in"))
      (node (ref "M5") (pin "13") (pinfunction "GND_13") (pintype "power_in"))
      (node (ref "M5") (pin "PPAD") (pinfunction "GND(THRML)_PPAD") (pintype "power_in"))
      (node (ref "Q5") (pin "2") (pinfunction "E_2") (pintype "passive"))
      (node (ref "R12") (pin "1") (pinfunction "1_1") (pintype "passive"))
      (node (ref "R15") (pin "1") (pinfunction "1_1") (pintype "passive"))
      (node (ref "R19") (pin "1") (pinfunction "1_1") (pintype "passive"))
      (node (ref "R20") (pin "1") (pinfunction "1_1") (pintype "passive"))
      (node (ref "R22") (pin "1") (pinfunction "1_1") (pintype "passive"))
      (node (ref "R23") (pin "1") (pinfunction "1_1") (pintype "passive"))
      (node (ref "R25") (pin "1") (pinfunction "1_1") (pintype "passive"))
      (node (ref "R26") (pin "1") (pinfunction "1_1") (pintype "passive"))
      (node (ref "R28") (pin "1") (pinfunction "1_1") (pintype "passive"))
      (node (ref "R29") (pin "1") (pinfunction "1_1") (pintype "passive"))
      (node (ref "R3") (pin "1") (pinfunction "1_1") (pintype "passive"))
      (node (ref "R31") (pin "1") (pinfunction "1_1") (pintype "passive"))
      (node (ref "R32") (pin "1") (pinfunction "1_1") (pintype "passive"))
      (node (ref "R35") (pin "2") (pinfunction "2_2") (pintype "passive"))
      (node (ref "R36") (pin "2") (pinfunction "2_2") (pintype "passive"))
      (node (ref "R37") (pin "2") (pinfunction "2_2") (pintype "passive"))
      (node (ref "R4") (pin "1") (pinfunction "1_1") (pintype "passive"))
      (node (ref "R8") (pin "1") (pinfunction "1_1") (pintype "passive"))
      (node (ref "S1") (pin "1") (pinfunction "1_1") (pintype "bidirectional"))
      (node (ref "S1") (pin "3") (pinfunction "1_3") (pintype "bidirectional"))
      (node (ref "TP12") (pin "P$1") (pinfunction "1_P$1") (pintype "bidirectional"))
      (node (ref "TP13") (pin "P$1") (pinfunction "1_P$1") (pintype "bidirectional"))
      (node (ref "U2") (pin "2") (pinfunction "GND_2") (pintype "power_in"))
      (node (ref "U3") (pin "2") (pinfunction "VSS_2") (pintype "power_in"))
      (node (ref "U4") (pin "15") (pinfunction "15_15") (pintype "passive"))
      (node (ref "U4") (pin "4") (pinfunction "CSN_4") (pintype "passive"))
      (node (ref "U5") (pin "10") (pinfunction "ADDR1_10") (pintype "bidirectional"))
      (node (ref "U5") (pin "17") (pinfunction "GND_17") (pintype "bidirectional"))
      (node (ref "U5") (pin "26") (pinfunction "ADDR0_26") (pintype "bidirectional"))
      (node (ref "U5") (pin "29") (pinfunction "GND_29") (pintype "bidirectional"))
      (node (ref "U5") (pin "3") (pinfunction "GND_3") (pintype "bidirectional"))
      (node (ref "U7") (pin "2") (pinfunction "GND_2") (pintype "power_in"))
      (node (ref "U7") (pin "THERM") (pinfunction "TP_THERM") (pintype "power_in"))
      (node (ref "U9") (pin "1") (pinfunction "GND_1") (pintype "bidirectional"))
      (node (ref "U9") (pin "15") (pinfunction "GND_15") (pintype "bidirectional"))
      (node (ref "U9") (pin "38") (pinfunction "GND_38") (pintype "bidirectional"))
      (node (ref "U9") (pin "GND") (pinfunction "GND_GND") (pintype "bidirectional"))
    )
    (net (code "23") (name "GREEN") (class "Default")
      (node (ref "R6") (pin "2") (pinfunction "2_2") (pintype "passive"))
      (node (ref "TP42") (pin "P$1") (pinfunction "1_P$1") (pintype "bidirectional"))
      (node (ref "U5") (pin "22") (pinfunction "I/O[15]_22") (pintype "bidirectional"))
    )
    (net (code "24") (name "IO1-RST") (class "Default")
      (node (ref "TP26") (pin "P$1") (pinfunction "1_P$1") (pintype "bidirectional"))
      (node (ref "U5") (pin "23") (pinfunction "~{RESET}_23") (pintype "bidirectional"))
      (node (ref "U9") (pin "24") (pinfunction "2_24") (pintype "bidirectional"))
    )
    (net (code "25") (name "LEDEXT") (class "Default")
      (node (ref "J15") (pin "2") (pinfunction "2_2") (pintype "passive"))
      (node (ref "TP5") (pin "P$1") (pinfunction "1_P$1") (pintype "bidirectional"))
      (node (ref "U9") (pin "13") (pinfunction "14-IO_13") (pintype "bidirectional"))
    )
    (net (code "26") (name "Net-(C10-Pad1)") (class "Default")
      (node (ref "C10") (pin "1") (pinfunction "1_1") (pintype "passive"))
      (node (ref "Q4") (pin "1") (pinfunction "S_1") (pintype "bidirectional"))
      (node (ref "Q4") (pin "2") (pinfunction "S_2") (pintype "bidirectional"))
      (node (ref "Q4") (pin "3") (pinfunction "S_3") (pintype "bidirectional"))
      (node (ref "R17") (pin "2") (pinfunction "2_2") (pintype "passive"))
      (node (ref "R34") (pin "2") (pinfunction "2_2") (pintype "passive"))
    )
    (net (code "27") (name "Net-(D2-PadC)") (class "Default")
      (node (ref "D2") (pin "C") (pinfunction "C_C") (pintype "passive"))
      (node (ref "R2") (pin "1") (pinfunction "1_1") (pintype "passive"))
    )
    (net (code "28") (name "Net-(D3-A1)") (class "Default")
      (node (ref "C10") (pin "2") (pinfunction "2_2") (pintype "passive"))
      (node (ref "D3") (pin "1") (pinfunction "A1_1") (pintype "passive"))
      (node (ref "Q4") (pin "4") (pinfunction "G_4") (pintype "bidirectional"))
      (node (ref "Q5") (pin "3") (pinfunction "C_3") (pintype "passive"))
      (node (ref "R17") (pin "1") (pinfunction "1_1") (pintype "passive"))
    )
    (net (code "29") (name "Net-(D3-C)") (class "Default")
      (node (ref "D3") (pin "3") (pinfunction "C_3") (pintype "passive"))
      (node (ref "S1") (pin "2") (pinfunction "2_2") (pintype "bidirectional"))
      (node (ref "S1") (pin "4") (pinfunction "2_4") (pintype "bidirectional"))
    )
    (net (code "30") (name "Net-(D4-PadC)") (class "Default")
      (node (ref "D4") (pin "C") (pinfunction "C_C") (pintype "passive"))
      (node (ref "R37") (pin "1") (pinfunction "1_1") (pintype "passive"))
    )
    (net (code "31") (name "Net-(D5-PadC)") (class "Default")
      (node (ref "D5") (pin "C") (pinfunction "C_C") (pintype "passive"))
      (node (ref "R35") (pin "1") (pinfunction "1_1") (pintype "passive"))
    )
    (net (code "32") (name "Net-(D6-PadC)") (class "Default")
      (node (ref "D6") (pin "C") (pinfunction "C_C") (pintype "passive"))
      (node (ref "R36") (pin "1") (pinfunction "1_1") (pintype "passive"))
    )
    (net (code "33") (name "Net-(J3-1)") (class "Default")
      (node (ref "J3") (pin "2") (pinfunction "1_2") (pintype "passive"))
      (node (ref "M0") (pin "2") (pinfunction "A_OUT1_2") (pintype "output"))
      (node (ref "M0") (pin "7") (pinfunction "B_OUT1_7") (pintype "output"))
    )
    (net (code "34") (name "Net-(J3-2)") (class "Default")
      (node (ref "J3") (pin "1") (pinfunction "2_1") (pintype "passive"))
      (node (ref "M0") (pin "4") (pinfunction "A_OUT2_4") (pintype "output"))
      (node (ref "M0") (pin "5") (pinfunction "B_OUT2_5") (pintype "output"))
    )
    (net (code "35") (name "Net-(J4-1)") (class "Default")
      (node (ref "J4") (pin "2") (pinfunction "1_2") (pintype "passive"))
      (node (ref "M1") (pin "2") (pinfunction "A_OUT1_2") (pintype "output"))
      (node (ref "M1") (pin "7") (pinfunction "B_OUT1_7") (pintype "output"))
    )
    (net (code "36") (name "Net-(J4-2)") (class "Default")
      (node (ref "J4") (pin "1") (pinfunction "2_1") (pintype "passive"))
      (node (ref "M1") (pin "4") (pinfunction "A_OUT2_4") (pintype "output"))
      (node (ref "M1") (pin "5") (pinfunction "B_OUT2_5") (pintype "output"))
    )
    (net (code "37") (name "Net-(J5-1)") (class "Default")
      (node (ref "J5") (pin "2") (pinfunction "1_2") (pintype "passive"))
      (node (ref "M2") (pin "2") (pinfunction "A_OUT1_2") (pintype "output"))
      (node (ref "M2") (pin "7") (pinfunction "B_OUT1_7") (pintype "output"))
    )
    (net (code "38") (name "Net-(J5-2)") (class "Default")
      (node (ref "J5") (pin "1") (pinfunction "2_1") (pintype "passive"))
      (node (ref "M2") (pin "4") (pinfunction "A_OUT2_4") (pintype "output"))
      (node (ref "M2") (pin "5") (pinfunction "B_OUT2_5") (pintype "output"))
    )
    (net (code "39") (name "Net-(J6-1)") (class "Default")
      (node (ref "J6") (pin "2") (pinfunction "1_2") (pintype "passive"))
      (node (ref "M3") (pin "2") (pinfunction "A_OUT1_2") (pintype "output"))
      (node (ref "M3") (pin "7") (pinfunction "B_OUT1_7") (pintype "output"))
    )
    (net (code "40") (name "Net-(J6-2)") (class "Default")
      (node (ref "J6") (pin "1") (pinfunction "2_1") (pintype "passive"))
      (node (ref "M3") (pin "4") (pinfunction "A_OUT2_4") (pintype "output"))
      (node (ref "M3") (pin "5") (pinfunction "B_OUT2_5") (pintype "output"))
    )
    (net (code "41") (name "Net-(J7-1)") (class "Default")
      (node (ref "J7") (pin "2") (pinfunction "1_2") (pintype "passive"))
      (node (ref "M4") (pin "2") (pinfunction "A_OUT1_2") (pintype "output"))
      (node (ref "M4") (pin "7") (pinfunction "B_OUT1_7") (pintype "output"))
    )
    (net (code "42") (name "Net-(J7-2)") (class "Default")
      (node (ref "J7") (pin "1") (pinfunction "2_1") (pintype "passive"))
      (node (ref "M4") (pin "4") (pinfunction "A_OUT2_4") (pintype "output"))
      (node (ref "M4") (pin "5") (pinfunction "B_OUT2_5") (pintype "output"))
    )
    (net (code "43") (name "Net-(J8-1)") (class "Default")
      (node (ref "J8") (pin "2") (pinfunction "1_2") (pintype "passive"))
      (node (ref "M5") (pin "2") (pinfunction "A_OUT1_2") (pintype "output"))
      (node (ref "M5") (pin "7") (pinfunction "B_OUT1_7") (pintype "output"))
    )
    (net (code "44") (name "Net-(J8-2)") (class "Default")
      (node (ref "J8") (pin "1") (pinfunction "2_1") (pintype "passive"))
      (node (ref "M5") (pin "4") (pinfunction "A_OUT2_4") (pintype "output"))
      (node (ref "M5") (pin "5") (pinfunction "B_OUT2_5") (pintype "output"))
    )
    (net (code "45") (name "Net-(M0-A_ISENSE)") (class "Default")
      (node (ref "M0") (pin "3") (pinfunction "A_ISENSE_3") (pintype "bidirectional"))
      (node (ref "M0") (pin "6") (pinfunction "B_ISENSE_6") (pintype "bidirectional"))
      (node (ref "R15") (pin "2") (pinfunction "2_2") (pintype "passive"))
      (node (ref "R8") (pin "2") (pinfunction "2_2") (pintype "passive"))
    )
    (net (code "46") (name "Net-(M0-NSLEEP)") (class "Default")
      (node (ref "M0") (pin "1") (pinfunction "NSLEEP_1") (pintype "input"))
      (node (ref "R16") (pin "2") (pinfunction "2_2") (pintype "passive"))
    )
    (net (code "47") (name "Net-(M0-VCP)") (class "Default")
      (node (ref "C20") (pin "2") (pinfunction "2_2") (pintype "passive"))
      (node (ref "M0") (pin "11") (pinfunction "VCP_11") (pintype "bidirectional"))
    )
    (net (code "48") (name "Net-(M0-VINT)") (class "Default")
      (node (ref "C4") (pin "1") (pinfunction "1_1") (pintype "passive"))
      (node (ref "M0") (pin "14") (pinfunction "VINT_14") (pintype "power_in"))
    )
    (net (code "49") (name "Net-(M1-A_ISENSE)") (class "Default")
      (node (ref "M1") (pin "3") (pinfunction "A_ISENSE_3") (pintype "bidirectional"))
      (node (ref "M1") (pin "6") (pinfunction "B_ISENSE_6") (pintype "bidirectional"))
      (node (ref "R19") (pin "2") (pinfunction "2_2") (pintype "passive"))
      (node (ref "R20") (pin "2") (pinfunction "2_2") (pintype "passive"))
    )
    (net (code "50") (name "Net-(M1-NSLEEP)") (class "Default")
      (node (ref "M1") (pin "1") (pinfunction "NSLEEP_1") (pintype "input"))
      (node (ref "R21") (pin "2") (pinfunction "2_2") (pintype "passive"))
    )
    (net (code "51") (name "Net-(M1-VCP)") (class "Default")
      (node (ref "C16") (pin "2") (pinfunction "2_2") (pintype "passive"))
      (node (ref "M1") (pin "11") (pinfunction "VCP_11") (pintype "bidirectional"))
    )
    (net (code "52") (name "Net-(M1-VINT)") (class "Default")
      (node (ref "C17") (pin "1") (pinfunction "1_1") (pintype "passive"))
      (node (ref "M1") (pin "14") (pinfunction "VINT_14") (pintype "power_in"))
    )
    (net (code "53") (name "Net-(M2-A_ISENSE)") (class "Default")
      (node (ref "M2") (pin "3") (pinfunction "A_ISENSE_3") (pintype "bidirectional"))
      (node (ref "M2") (pin "6") (pinfunction "B_ISENSE_6") (pintype "bidirectional"))
      (node (ref "R22") (pin "2") (pinfunction "2_2") (pintype "passive"))
      (node (ref "R23") (pin "2") (pinfunction "2_2") (pintype "passive"))
    )
    (net (code "54") (name "Net-(M2-NSLEEP)") (class "Default")
      (node (ref "M2") (pin "1") (pinfunction "NSLEEP_1") (pintype "input"))
      (node (ref "R24") (pin "2") (pinfunction "2_2") (pintype "passive"))
    )
    (net (code "55") (name "Net-(M2-VCP)") (class "Default")
      (node (ref "C22") (pin "2") (pinfunction "2_2") (pintype "passive"))
      (node (ref "M2") (pin "11") (pinfunction "VCP_11") (pintype "bidirectional"))
    )
    (net (code "56") (name "Net-(M2-VINT)") (class "Default")
      (node (ref "C23") (pin "1") (pinfunction "1_1") (pintype "passive"))
      (node (ref "M2") (pin "14") (pinfunction "VINT_14") (pintype "power_in"))
    )
    (net (code "57") (name "Net-(M3-A_ISENSE)") (class "Default")
      (node (ref "M3") (pin "3") (pinfunction "A_ISENSE_3") (pintype "bidirectional"))
      (node (ref "M3") (pin "6") (pinfunction "B_ISENSE_6") (pintype "bidirectional"))
      (node (ref "R25") (pin "2") (pinfunction "2_2") (pintype "passive"))
      (node (ref "R26") (pin "2") (pinfunction "2_2") (pintype "passive"))
    )
    (net (code "58") (name "Net-(M3-NSLEEP)") (class "Default")
      (node (ref "M3") (pin "1") (pinfunction "NSLEEP_1") (pintype "input"))
      (node (ref "R27") (pin "2") (pinfunction "2_2") (pintype "passive"))
    )
    (net (code "59") (name "Net-(M3-VCP)") (class "Default")
      (node (ref "C26") (pin "2") (pinfunction "2_2") (pintype "passive"))
      (node (ref "M3") (pin "11") (pinfunction "VCP_11") (pintype "bidirectional"))
    )
    (net (code "60") (name "Net-(M3-VINT)") (class "Default")
      (node (ref "C27") (pin "1") (pinfunction "1_1") (pintype "passive"))
      (node (ref "M3") (pin "14") (pinfunction "VINT_14") (pintype "power_in"))
    )
    (net (code "61") (name "Net-(M4-A_ISENSE)") (class "Default")
      (node (ref "M4") (pin "3") (pinfunction "A_ISENSE_3") (pintype "bidirectional"))
      (node (ref "M4") (pin "6") (pinfunction "B_ISENSE_6") (pintype "bidirectional"))
      (node (ref "R28") (pin "2") (pinfunction "2_2") (pintype "passive"))
      (node (ref "R29") (pin "2") (pinfunction "2_2") (pintype "passive"))
    )
    (net (code "62") (name "Net-(M4-NSLEEP)") (class "Default")
      (node (ref "M4") (pin "1") (pinfunction "NSLEEP_1") (pintype "input"))
      (node (ref "R30") (pin "2") (pinfunction "2_2") (pintype "passive"))
    )
    (net (code "63") (name "Net-(M4-VCP)") (class "Default")
      (node (ref "C31") (pin "2") (pinfunction "2_2") (pintype "passive"))
      (node (ref "M4") (pin "11") (pinfunction "VCP_11") (pintype "bidirectional"))
    )
    (net (code "64") (name "Net-(M4-VINT)") (class "Default")
      (node (ref "C32") (pin "1") (pinfunction "1_1") (pintype "passive"))
      (node (ref "M4") (pin "14") (pinfunction "VINT_14") (pintype "power_in"))
    )
    (net (code "65") (name "Net-(M5-A_ISENSE)") (class "Default")
      (node (ref "M5") (pin "3") (pinfunction "A_ISENSE_3") (pintype "bidirectional"))
      (node (ref "M5") (pin "6") (pinfunction "B_ISENSE_6") (pintype "bidirectional"))
      (node (ref "R31") (pin "2") (pinfunction "2_2") (pintype "passive"))
      (node (ref "R32") (pin "2") (pinfunction "2_2") (pintype "passive"))
    )
    (net (code "66") (name "Net-(M5-NSLEEP)") (class "Default")
      (node (ref "M5") (pin "1") (pinfunction "NSLEEP_1") (pintype "input"))
      (node (ref "R33") (pin "2") (pinfunction "2_2") (pintype "passive"))
    )
    (net (code "67") (name "Net-(M5-VCP)") (class "Default")
      (node (ref "C35") (pin "2") (pinfunction "2_2") (pintype "passive"))
      (node (ref "M5") (pin "11") (pinfunction "VCP_11") (pintype "bidirectional"))
    )
    (net (code "68") (name "Net-(M5-VINT)") (class "Default")
      (node (ref "C36") (pin "1") (pinfunction "1_1") (pintype "passive"))
      (node (ref "M5") (pin "14") (pinfunction "VINT_14") (pintype "power_in"))
    )
    (net (code "69") (name "Net-(Q1-B)") (class "Default")
      (node (ref "Q1") (pin "1") (pinfunction "B_1") (pintype "passive"))
      (node (ref "R10") (pin "2") (pinfunction "2_2") (pintype "passive"))
    )
    (net (code "70") (name "Net-(Q2-B)") (class "Default")
      (node (ref "Q2") (pin "1") (pinfunction "B_1") (pintype "passive"))
      (node (ref "R9") (pin "2") (pinfunction "2_2") (pintype "passive"))
    )
    (net (code "71") (name "Net-(Q3-S)") (class "Default")
      (node (ref "C6") (pin "1") (pinfunction "1_1") (pintype "passive"))
      (node (ref "D1") (pin "C") (pinfunction "C_C") (pintype "passive"))
      (node (ref "Q3") (pin "2") (pinfunction "S_2") (pintype "passive"))
      (node (ref "U2") (pin "1") (pinfunction "IN_1") (pintype "power_in"))
      (node (ref "U2") (pin "3") (pinfunction "EN_3") (pintype "input"))
    )
    (net (code "72") (name "Net-(Q5-B)") (class "Default")
      (node (ref "Q5") (pin "1") (pinfunction "B_1") (pintype "passive"))
      (node (ref "R18") (pin "1") (pinfunction "1_1") (pintype "passive"))
    )
    (net (code "73") (name "Net-(TP7-1)") (class "Default")
      (node (ref "TP7") (pin "P$1") (pinfunction "1_P$1") (pintype "bidirectional"))
      (node (ref "U9") (pin "7") (pinfunction "35-IA_7") (pintype "bidirectional"))
    )
    (net (code "74") (name "Net-(TP9-1)") (class "Default")
      (node (ref "TP9") (pin "P$1") (pinfunction "1_P$1") (pintype "bidirectional"))
      (node (ref "U9") (pin "5") (pinfunction "39-I_5") (pintype "bidirectional"))
    )
    (net (code "75") (name "Net-(TP10-1)") (class "Default")
      (node (ref "TP10") (pin "P$1") (pinfunction "1_P$1") (pintype "bidirectional"))
      (node (ref "U9") (pin "4") (pinfunction "36-I_4") (pintype "bidirectional"))
    )
    (net (code "76") (name "Net-(U1-2)") (class "Default")
      (node (ref "R7") (pin "1") (pinfunction "1_1") (pintype "passive"))
      (node (ref "U1") (pin "BLUE") (pinfunction "2_BLUE") (pintype "passive"))
    )
    (net (code "77") (name "Net-(U1-3)") (class "Default")
      (node (ref "R6") (pin "1") (pinfunction "1_1") (pintype "passive"))
      (node (ref "U1") (pin "GREEN") (pinfunction "3_GREEN") (pintype "passive"))
    )
    (net (code "78") (name "Net-(U1-4)") (class "Default")
      (node (ref "R5") (pin "1") (pinfunction "1_1") (pintype "passive"))
      (node (ref "U1") (pin "RED") (pinfunction "4_RED") (pintype "passive"))
    )
    (net (code "79") (name "Net-(U3-PROG)") (class "Default")
      (node (ref "JP1") (pin "1") (pinfunction "1_1") (pintype "passive"))
      (node (ref "JP2") (pin "1") (pinfunction "1_1") (pintype "passive"))
      (node (ref "R4") (pin "2") (pinfunction "2_2") (pintype "passive"))
      (node (ref "U3") (pin "5") (pinfunction "PROG_5") (pintype "input"))
    )
    (net (code "80") (name "Net-(U3-STAT)") (class "Default")
      (node (ref "R2") (pin "2") (pinfunction "2_2") (pintype "passive"))
      (node (ref "U3") (pin "1") (pinfunction "STAT_1") (pintype "output"))
    )
    (net (code "81") (name "Net-(U4-CELL1)") (class "Default")
      (node (ref "C11") (pin "1") (pinfunction "1_1") (pintype "passive"))
      (node (ref "R1") (pin "2") (pinfunction "2_2") (pintype "passive"))
      (node (ref "U4") (pin "1") (pinfunction "REG3_1") (pintype "bidirectional"))
      (node (ref "U4") (pin "13") (pinfunction "CELLX_13") (pintype "passive"))
      (node (ref "U4") (pin "5") (pinfunction "VBATT_5") (pintype "passive"))
      (node (ref "U4") (pin "6") (pinfunction "CELL2_6") (pintype "bidirectional"))
      (node (ref "U4") (pin "7") (pinfunction "CELL1_7") (pintype "bidirectional"))
    )
    (net (code "82") (name "Net-(U4-REG2)") (class "Default")
      (node (ref "C1") (pin "1") (pinfunction "1_1") (pintype "passive"))
      (node (ref "U4") (pin "3") (pinfunction "REG2_3") (pintype "bidirectional"))
    )
    (net (code "83") (name "Net-(U7A-D+)") (class "Default")
      (node (ref "J1") (pin "D+") (pinfunction "D+_D+") (pintype "bidirectional"))
      (node (ref "U7") (pin "3") (pinfunction "D+_3") (pintype "bidirectional"))
    )
    (net (code "84") (name "Net-(U7A-D-)") (class "Default")
      (node (ref "J1") (pin "D-") (pinfunction "D-_D-") (pintype "bidirectional"))
      (node (ref "U7") (pin "4") (pinfunction "D-_4") (pintype "bidirectional"))
    )
    (net (code "85") (name "PWM0-1") (class "Default")
      (node (ref "J11") (pin "3") (pinfunction "3_3") (pintype "passive"))
      (node (ref "M0") (pin "16") (pinfunction "A_IN1_16") (pintype "input"))
      (node (ref "M0") (pin "9") (pinfunction "B_IN1_9") (pintype "input"))
      (node (ref "TP1") (pin "P$1") (pinfunction "1_P$1") (pintype "bidirectional"))
      (node (ref "U9") (pin "8") (pinfunction "32-IOA_8") (pintype "bidirectional"))
    )
    (net (code "86") (name "PWM0-2") (class "Default")
      (node (ref "J12") (pin "3") (pinfunction "3_3") (pintype "passive"))
      (node (ref "M0") (pin "10") (pinfunction "B_IN2_10") (pintype "input"))
      (node (ref "M0") (pin "15") (pinfunction "A_IN2_15") (pintype "input"))
      (node (ref "TP2") (pin "P$1") (pinfunction "1_P$1") (pintype "bidirectional"))
      (node (ref "U9") (pin "9") (pinfunction "33-IOA_9") (pintype "bidirectional"))
    )
    (net (code "87") (name "PWM1-1") (class "Default")
      (node (ref "J13") (pin "3") (pinfunction "3_3") (pintype "passive"))
      (node (ref "M1") (pin "16") (pinfunction "A_IN1_16") (pintype "input"))
      (node (ref "M1") (pin "9") (pinfunction "B_IN1_9") (pintype "input"))
      (node (ref "TP3") (pin "P$1") (pinfunction "1_P$1") (pintype "bidirectional"))
      (node (ref "U9") (pin "10") (pinfunction "25-IOD_10") (pintype "bidirectional"))
    )
    (net (code "88") (name "PWM1-2") (class "Default")
      (node (ref "J14") (pin "3") (pinfunction "3_3") (pintype "passive"))
      (node (ref "M1") (pin "10") (pinfunction "B_IN2_10") (pintype "input"))
      (node (ref "M1") (pin "15") (pinfunction "A_IN2_15") (pintype "input"))
      (node (ref "TP6") (pin "P$1") (pinfunction "1_P$1") (pintype "bidirectional"))
      (node (ref "U9") (pin "11") (pinfunction "26-IOD_11") (pintype "bidirectional"))
    )
    (net (code "89") (name "PWM2-1") (class "Default")
      (node (ref "M2") (pin "16") (pinfunction "A_IN1_16") (pintype "input"))
      (node (ref "M2") (pin "9") (pinfunction "B_IN1_9") (pintype "input"))
      (node (ref "TP17") (pin "P$1") (pinfunction "1_P$1") (pintype "bidirectional"))
      (node (ref "U9") (pin "12") (pinfunction "27-IO_12") (pintype "bidirectional"))
    )
    (net (code "90") (name "PWM2-2") (class "Default")
      (node (ref "M2") (pin "10") (pinfunction "B_IN2_10") (pintype "input"))
      (node (ref "M2") (pin "15") (pinfunction "A_IN2_15") (pintype "input"))
      (node (ref "TP23") (pin "P$1") (pinfunction "1_P$1") (pintype "bidirectional"))
      (node (ref "U9") (pin "16") (pinfunction "13-IO_16") (pintype "bidirectional"))
    )
    (net (code "91") (name "PWM3-1") (class "Default")
      (node (ref "M3") (pin "16") (pinfunction "A_IN1_16") (pintype "input"))
      (node (ref "M3") (pin "9") (pinfunction "B_IN1_9") (pintype "input"))
      (node (ref "TP16") (pin "P$1") (pinfunction "1_P$1") (pintype "bidirectional"))
      (node (ref "U9") (pin "26") (pinfunction "4-IO_26") (pintype "bidirectional"))
    )
    (net (code "92") (name "PWM3-2") (class "Default")
      (node (ref "M3") (pin "10") (pinfunction "B_IN2_10") (pintype "input"))
      (node (ref "M3") (pin "15") (pinfunction "A_IN2_15") (pintype "input"))
      (node (ref "TP15") (pin "P$1") (pinfunction "1_P$1") (pintype "bidirectional"))
      (node (ref "U9") (pin "27") (pinfunction "16-IO_27") (pintype "bidirectional"))
    )
    (net (code "93") (name "PWM4-1") (class "Default")
      (node (ref "M4") (pin "16") (pinfunction "A_IN1_16") (pintype "input"))
      (node (ref "M4") (pin "9") (pinfunction "B_IN1_9") (pintype "input"))
      (node (ref "TP22") (pin "P$1") (pinfunction "1_P$1") (pintype "bidirectional"))
      (node (ref "U9") (pin "28") (pinfunction "17-IO_28") (pintype "bidirectional"))
    )
    (net (code "94") (name "PWM4-2") (class "Default")
      (node (ref "M4") (pin "10") (pinfunction "B_IN2_10") (pintype "input"))
      (node (ref "M4") (pin "15") (pinfunction "A_IN2_15") (pintype "input"))
      (node (ref "TP21") (pin "P$1") (pinfunction "1_P$1") (pintype "bidirectional"))
      (node (ref "U9") (pin "30") (pinfunction "18-IO_30") (pintype "bidirectional"))
    )
    (net (code "95") (name "PWM5-1") (class "Default")
      (node (ref "M5") (pin "16") (pinfunction "A_IN1_16") (pintype "input"))
      (node (ref "M5") (pin "9") (pinfunction "B_IN1_9") (pintype "input"))
      (node (ref "TP20") (pin "P$1") (pinfunction "1_P$1") (pintype "bidirectional"))
      (node (ref "U9") (pin "31") (pinfunction "19-IO_31") (pintype "bidirectional"))
    )
    (net (code "96") (name "PWM5-2") (class "Default")
      (node (ref "M5") (pin "10") (pinfunction "B_IN2_10") (pintype "input"))
      (node (ref "M5") (pin "15") (pinfunction "A_IN2_15") (pintype "input"))
      (node (ref "TP14") (pin "P$1") (pinfunction "1_P$1") (pintype "bidirectional"))
      (node (ref "U9") (pin "37") (pinfunction "23-IO_37") (pintype "bidirectional"))
    )
    (net (code "97") (name "PWR") (class "Default")
      (node (ref "JP2") (pin "2") (pinfunction "2_2") (pintype "passive"))
      (node (ref "R18") (pin "2") (pinfunction "2_2") (pintype "passive"))
      (node (ref "TP4") (pin "P$1") (pinfunction "1_P$1") (pintype "bidirectional"))
      (node (ref "U9") (pin "14") (pinfunction "12_14") (pintype "bidirectional"))
    )
    (net (code "98") (name "RED") (class "Default")
      (node (ref "R5") (pin "2") (pinfunction "2_2") (pintype "passive"))
      (node (ref "TP40") (pin "P$1") (pinfunction "1_P$1") (pintype "bidirectional"))
      (node (ref "U5") (pin "20") (pinfunction "I/O[13]_20") (pintype "bidirectional"))
    )
    (net (code "99") (name "RTS") (class "Default")
      (node (ref "Q1") (pin "2") (pinfunction "E_2") (pintype "passive"))
      (node (ref "R9") (pin "1") (pinfunction "1_1") (pintype "passive"))
      (node (ref "U7") (pin "19") (pinfunction "RTS_19") (pintype "output"))
    )
    (net (code "100") (name "RX") (class "Default")
      (node (ref "U7") (pin "21") (pinfunction "TXD_21") (pintype "output"))
      (node (ref "U9") (pin "34") (pinfunction "RX_34") (pintype "bidirectional"))
    )
    (net (code "101") (name "S1-SIG") (class "Default")
      (node (ref "J9") (pin "3") (pinfunction "3_3") (pintype "passive"))
      (node (ref "TP24") (pin "P$1") (pinfunction "1_P$1") (pintype "bidirectional"))
      (node (ref "U9") (pin "23") (pinfunction "15_23") (pintype "bidirectional"))
    )
    (net (code "102") (name "S2-SIG") (class "Default")
      (node (ref "J10") (pin "3") (pinfunction "3_3") (pintype "passive"))
      (node (ref "TP25") (pin "P$1") (pinfunction "1_P$1") (pintype "bidirectional"))
      (node (ref "U9") (pin "29") (pinfunction "5_29") (pintype "bidirectional"))
    )
    (net (code "103") (name "SCL") (class "Default")
      (node (ref "R14") (pin "2") (pinfunction "2_2") (pintype "passive"))
      (node (ref "TP18") (pin "P$1") (pinfunction "1_P$1") (pintype "bidirectional"))
      (node (ref "U4") (pin "11") (pinfunction "OD/SCL_11") (pintype "passive"))
      (node (ref "U5") (pin "25") (pinfunction "SCL_25") (pintype "bidirectional"))
      (node (ref "U9") (pin "36") (pinfunction "22-IO_36") (pintype "bidirectional"))
    )
    (net (code "104") (name "SDA") (class "Default")
      (node (ref "R13") (pin "1") (pinfunction "1_1") (pintype "passive"))
      (node (ref "TP19") (pin "P$1") (pinfunction "1_P$1") (pintype "bidirectional"))
      (node (ref "U4") (pin "12") (pinfunction "DQ/SDA_12") (pintype "passive"))
      (node (ref "U5") (pin "24") (pinfunction "SDA_24") (pintype "bidirectional"))
      (node (ref "U9") (pin "33") (pinfunction "21-IO_33") (pintype "bidirectional"))
    )
    (net (code "105") (name "TX") (class "Default")
      (node (ref "U7") (pin "20") (pinfunction "RXD_20") (pintype "input"))
      (node (ref "U9") (pin "35") (pinfunction "TX_35") (pintype "bidirectional"))
    )
    (net (code "106") (name "VBAT") (class "Default")
      (node (ref "C12") (pin "1") (pinfunction "1_1") (pintype "passive"))
      (node (ref "C14") (pin "+") (pinfunction "+_+") (pintype "passive"))
      (node (ref "C16") (pin "1") (pinfunction "1_1") (pintype "passive"))
      (node (ref "C18") (pin "1") (pinfunction "1_1") (pintype "passive"))
      (node (ref "C19") (pin "+") (pinfunction "+_+") (pintype "passive"))
      (node (ref "C20") (pin "1") (pinfunction "1_1") (pintype "passive"))
      (node (ref "C22") (pin "1") (pinfunction "1_1") (pintype "passive"))
      (node (ref "C24") (pin "1") (pinfunction "1_1") (pintype "passive"))
      (node (ref "C25") (pin "+") (pinfunction "+_+") (pintype "passive"))
      (node (ref "C26") (pin "1") (pinfunction "1_1") (pintype "passive"))
      (node (ref "C28") (pin "+") (pinfunction "+_+") (pintype "passive"))
      (node (ref "C29") (pin "1") (pinfunction "1_1") (pintype "passive"))
      (node (ref "C3") (pin "1") (pinfunction "1_1") (pintype "passive"))
      (node (ref "C30") (pin "+") (pinfunction "+_+") (pintype "passive"))
      (node (ref "C31") (pin "1") (pinfunction "1_1") (pintype "passive"))
      (node (ref "C33") (pin "1") (pinfunction "1_1") (pintype "passive"))
      (node (ref "C34") (pin "+") (pinfunction "+_+") (pintype "passive"))
      (node (ref "C35") (pin "1") (pinfunction "1_1") (pintype "passive"))
      (node (ref "C5") (pin "1") (pinfunction "1_1") (pintype "passive"))
      (node (ref "D5") (pin "A") (pinfunction "A_A") (pintype "passive"))
      (node (ref "J10") (pin "2") (pinfunction "2_2") (pintype "passive"))
      (node (ref "J11") (pin "2") (pinfunction "2_2") (pintype "passive"))
      (node (ref "J12") (pin "2") (pinfunction "2_2") (pintype "passive"))
      (node (ref "J13") (pin "2") (pinfunction "2_2") (pintype "passive"))
      (node (ref "J14") (pin "2") (pinfunction "2_2") (pintype "passive"))
      (node (ref "J9") (pin "2") (pinfunction "2_2") (pintype "passive"))
      (node (ref "M0") (pin "12") (pinfunction "VM_12") (pintype "power_in"))
      (node (ref "M1") (pin "12") (pinfunction "VM_12") (pintype "power_in"))
      (node (ref "M2") (pin "12") (pinfunction "VM_12") (pintype "power_in"))
      (node (ref "M3") (pin "12") (pinfunction "VM_12") (pintype "power_in"))
      (node (ref "M4") (pin "12") (pinfunction "VM_12") (pintype "power_in"))
      (node (ref "M5") (pin "12") (pinfunction "VM_12") (pintype "power_in"))
      (node (ref "Q3") (pin "3") (pinfunction "D_3") (pintype "passive"))
      (node (ref "Q4") (pin "5") (pinfunction "D_5") (pintype "bidirectional"))
      (node (ref "Q4") (pin "6") (pinfunction "D_6") (pintype "bidirectional"))
      (node (ref "Q4") (pin "7") (pinfunction "D_7") (pintype "bidirectional"))
      (node (ref "Q4") (pin "8") (pinfunction "D_8") (pintype "bidirectional"))
      (node (ref "R1") (pin "1") (pinfunction "1_1") (pintype "passive"))
      (node (ref "R16") (pin "1") (pinfunction "1_1") (pintype "passive"))
      (node (ref "R21") (pin "1") (pinfunction "1_1") (pintype "passive"))
      (node (ref "R24") (pin "1") (pinfunction "1_1") (pintype "passive"))
      (node (ref "R27") (pin "1") (pinfunction "1_1") (pintype "passive"))
      (node (ref "R30") (pin "1") (pinfunction "1_1") (pintype "passive"))
      (node (ref "R33") (pin "1") (pinfunction "1_1") (pintype "passive"))
      (node (ref "U3") (pin "3") (pinfunction "VBAT_3") (pintype "power_in"))
    )
    (net (code "107") (name "VUSB") (class "Default")
      (node (ref "C9") (pin "1") (pinfunction "1_1") (pintype "passive"))
      (node (ref "D1") (pin "A") (pinfunction "A_A") (pintype "passive"))
      (node (ref "D2") (pin "A") (pinfunction "A_A") (pintype "passive"))
      (node (ref "D4") (pin "A") (pinfunction "A_A") (pintype "passive"))
      (node (ref "J1") (pin "VBUS") (pinfunction "VBUS_VBUS") (pintype "power_in"))
      (node (ref "JP1") (pin "2") (pinfunction "2_2") (pintype "passive"))
      (node (ref "Q3") (pin "1") (pinfunction "G_1") (pintype "passive"))
      (node (ref "R12") (pin "2") (pinfunction "2_2") (pintype "passive"))
      (node (ref "U3") (pin "4") (pinfunction "VDD_4") (pintype "power_in"))
      (node (ref "U7") (pin "8") (pinfunction "VBUS_8") (pintype "power_in"))
    )
    (net (code "108") (name "unconnected-(J1-PadID)") (class "Default")
      (node (ref "J1") (pin "ID") (pinfunction "ID_ID") (pintype "bidirectional"))
    )
    (net (code "109") (name "unconnected-(M0-NFAULT-Pad8)") (class "Default")
      (node (ref "M0") (pin "8") (pinfunction "NFAULT_8") (pintype "bidirectional"))
    )
    (net (code "110") (name "unconnected-(M1-NFAULT-Pad8)") (class "Default")
      (node (ref "M1") (pin "8") (pinfunction "NFAULT_8") (pintype "bidirectional"))
    )
    (net (code "111") (name "unconnected-(M2-NFAULT-Pad8)") (class "Default")
      (node (ref "M2") (pin "8") (pinfunction "NFAULT_8") (pintype "bidirectional"))
    )
    (net (code "112") (name "unconnected-(M3-NFAULT-Pad8)") (class "Default")
      (node (ref "M3") (pin "8") (pinfunction "NFAULT_8") (pintype "bidirectional"))
    )
    (net (code "113") (name "unconnected-(M4-NFAULT-Pad8)") (class "Default")
      (node (ref "M4") (pin "8") (pinfunction "NFAULT_8") (pintype "bidirectional"))
    )
    (net (code "114") (name "unconnected-(M5-NFAULT-Pad8)") (class "Default")
      (node (ref "M5") (pin "8") (pinfunction "NFAULT_8") (pintype "bidirectional"))
    )
    (net (code "115") (name "unconnected-(U2-P4-Pad4)") (class "Default")
      (node (ref "U2") (pin "4") (pinfunction "P4_4") (pintype "bidirectional"))
    )
    (net (code "116") (name "unconnected-(U4-AIN1-Pad9)") (class "Default")
      (node (ref "U4") (pin "9") (pinfunction "AIN1_9") (pintype "input"))
    )
    (net (code "117") (name "unconnected-(U4-AIN2-Pad10)") (class "Default")
      (node (ref "U4") (pin "10") (pinfunction "AIN2_10") (pintype "input"))
    )
    (net (code "118") (name "unconnected-(U4-ALRT1-Pad8)") (class "Default")
      (node (ref "U4") (pin "8") (pinfunction "ALRT1_8") (pintype "passive"))
    )
    (net (code "119") (name "unconnected-(U4-THRM-Pad14)") (class "Default")
      (node (ref "U4") (pin "14") (pinfunction "THRM_14") (pintype "passive"))
    )
    (net (code "120") (name "unconnected-(U5-OSCIO-Pad11)") (class "Default")
      (node (ref "U5") (pin "11") (pinfunction "OSCIO_11") (pintype "bidirectional"))
    )
    (net (code "121") (name "unconnected-(U5-~{INT}-Pad9)") (class "Default")
      (node (ref "U5") (pin "9") (pinfunction "~{INT}_9") (pintype "bidirectional"))
    )
    (net (code "122") (name "unconnected-(U7A-#RST-Pad9)") (class "Default")
      (node (ref "U7") (pin "9") (pinfunction "#RST_9") (pintype "bidirectional"))
    )
    (net (code "123") (name "unconnected-(U7A-#SUSPEND-Pad15)") (class "Default")
      (node (ref "U7") (pin "15") (pinfunction "#SUSPEND_15") (pintype "output"))
    )
    (net (code "124") (name "unconnected-(U7A-CTS-Pad18)") (class "Default")
      (node (ref "U7") (pin "18") (pinfunction "CTS_18") (pintype "input"))
    )
    (net (code "125") (name "unconnected-(U7A-DCD-Pad24)") (class "Default")
      (node (ref "U7") (pin "24") (pinfunction "DCD_24") (pintype "input"))
    )
    (net (code "126") (name "unconnected-(U7A-DSR-Pad22)") (class "Default")
      (node (ref "U7") (pin "22") (pinfunction "DSR_22") (pintype "input"))
    )
    (net (code "127") (name "unconnected-(U7A-GPIO0{slash}TXLED-Pad14)") (class "Default")
      (node (ref "U7") (pin "14") (pinfunction "GPIO0/TXLED_14") (pintype "bidirectional"))
    )
    (net (code "128") (name "unconnected-(U7A-GPIO1{slash}RXLED-Pad13)") (class "Default")
      (node (ref "U7") (pin "13") (pinfunction "GPIO1/RXLED_13") (pintype "bidirectional"))
    )
    (net (code "129") (name "unconnected-(U7A-GPIO2-Pad12)") (class "Default")
      (node (ref "U7") (pin "12") (pinfunction "GPIO2_12") (pintype "bidirectional"))
    )
    (net (code "130") (name "unconnected-(U7A-GPIO3-Pad11)") (class "Default")
      (node (ref "U7") (pin "11") (pinfunction "GPIO3_11") (pintype "bidirectional"))
    )
    (net (code "131") (name "unconnected-(U7A-NC-Pad10)") (class "Default")
      (node (ref "U7") (pin "10") (pinfunction "NC_10") (pintype "no_connect"))
    )
    (net (code "132") (name "unconnected-(U7A-RI-Pad1)") (class "Default")
      (node (ref "U7") (pin "1") (pinfunction "RI_1") (pintype "input"))
    )
    (net (code "133") (name "unconnected-(U7A-SUSPEND-Pad17)") (class "Default")
      (node (ref "U7") (pin "17") (pinfunction "SUSPEND_17") (pintype "output"))
    )
    (net (code "134") (name "unconnected-(U7A-VPP-Pad16)") (class "Default")
      (node (ref "U7") (pin "16") (pinfunction "VPP_16") (pintype "bidirectional"))
    )
    (net (code "135") (name "unconnected-(U9-NC-Pad32)") (class "Default")
      (node (ref "U9") (pin "32") (pinfunction "NC_32") (pintype "bidirectional"))
    )
    (net (code "136") (name "unconnected-(U9-SCK-Pad20)") (class "Default")
      (node (ref "U9") (pin "20") (pinfunction "SCK_20") (pintype "bidirectional"))
    )
    (net (code "137") (name "unconnected-(U9-SCS-Pad19)") (class "Default")
      (node (ref "U9") (pin "19") (pinfunction "SCS_19") (pintype "bidirectional"))
    )
    (net (code "138") (name "unconnected-(U9-SDI-Pad22)") (class "Default")
      (node (ref "U9") (pin "22") (pinfunction "SDI_22") (pintype "bidirectional"))
    )
    (net (code "139") (name "unconnected-(U9-SDO-Pad21)") (class "Default")
      (node (ref "U9") (pin "21") (pinfunction "SDO_21") (pintype "bidirectional"))
    )
    (net (code "140") (name "unconnected-(U9-SHD-Pad17)") (class "Default")
      (node (ref "U9") (pin "17") (pinfunction "SHD_17") (pintype "bidirectional"))
    )
    (net (code "141") (name "unconnected-(U9-SWP-Pad18)") (class "Default")
      (node (ref "U9") (pin "18") (pinfunction "SWP_18") (pintype "bidirectional"))
    )
  )
)
